# untitled.net
KiCad netlist of a schematic drawn in EAGLE
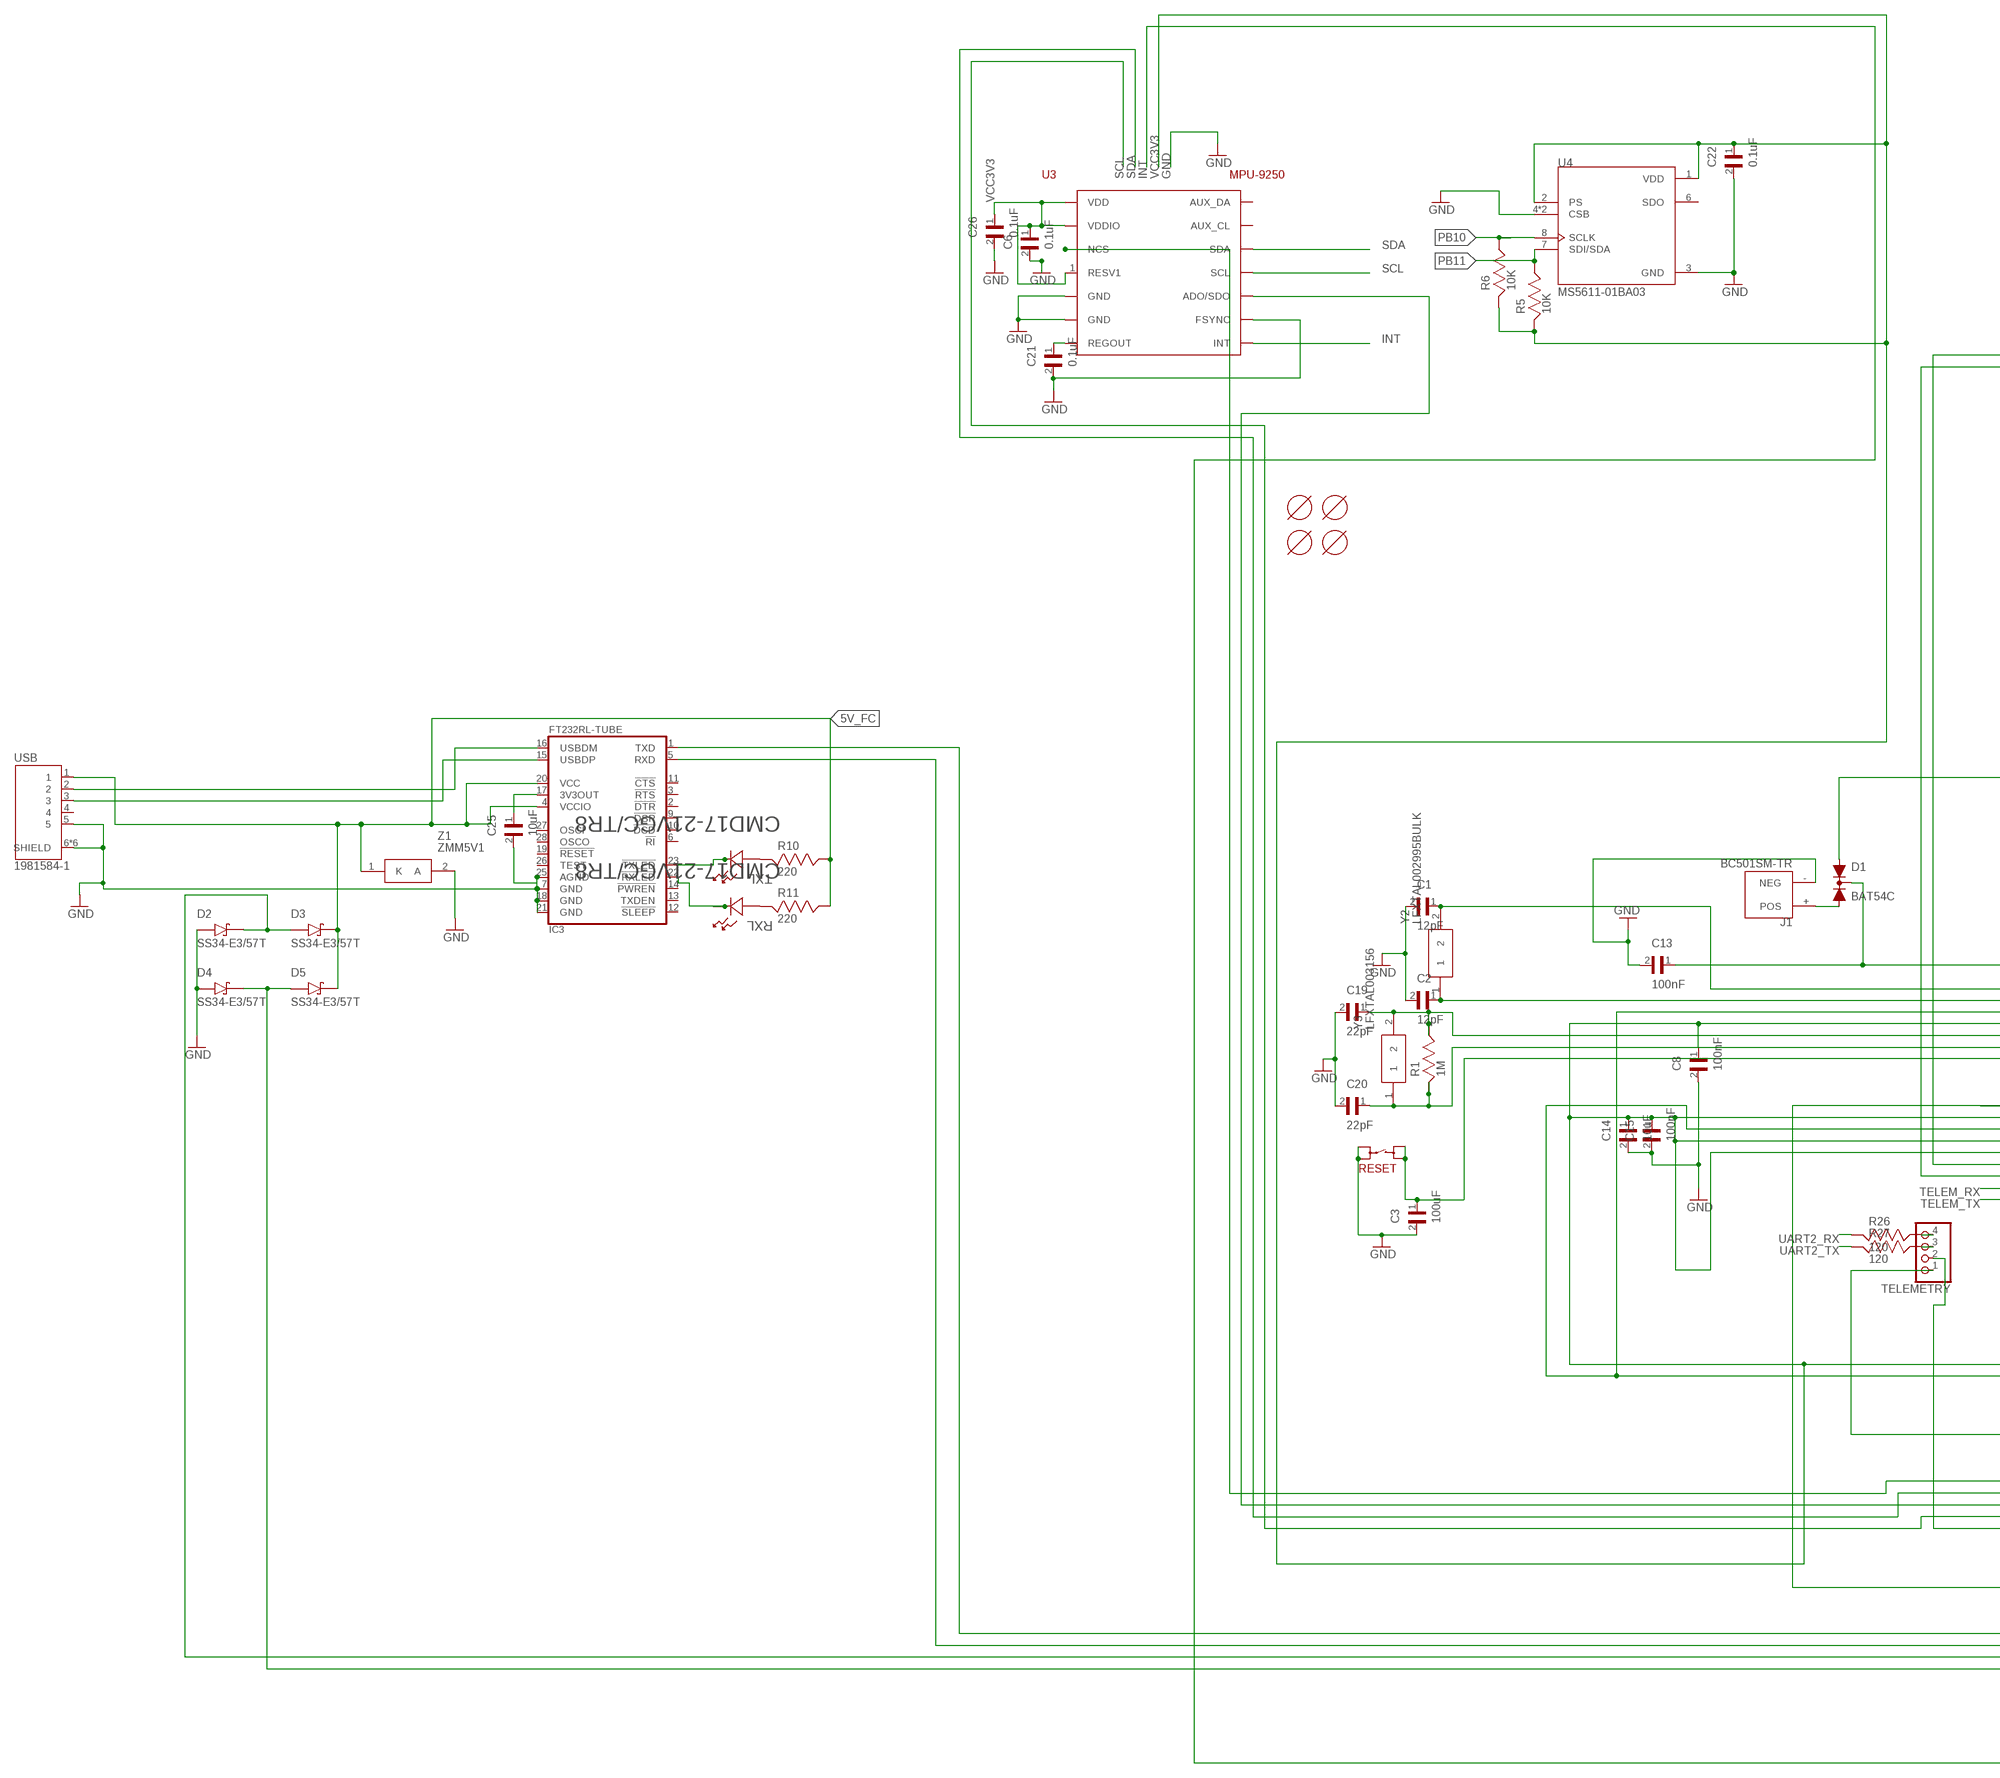
[diagram p0: schematic, sheet 1, part 1 of 2]
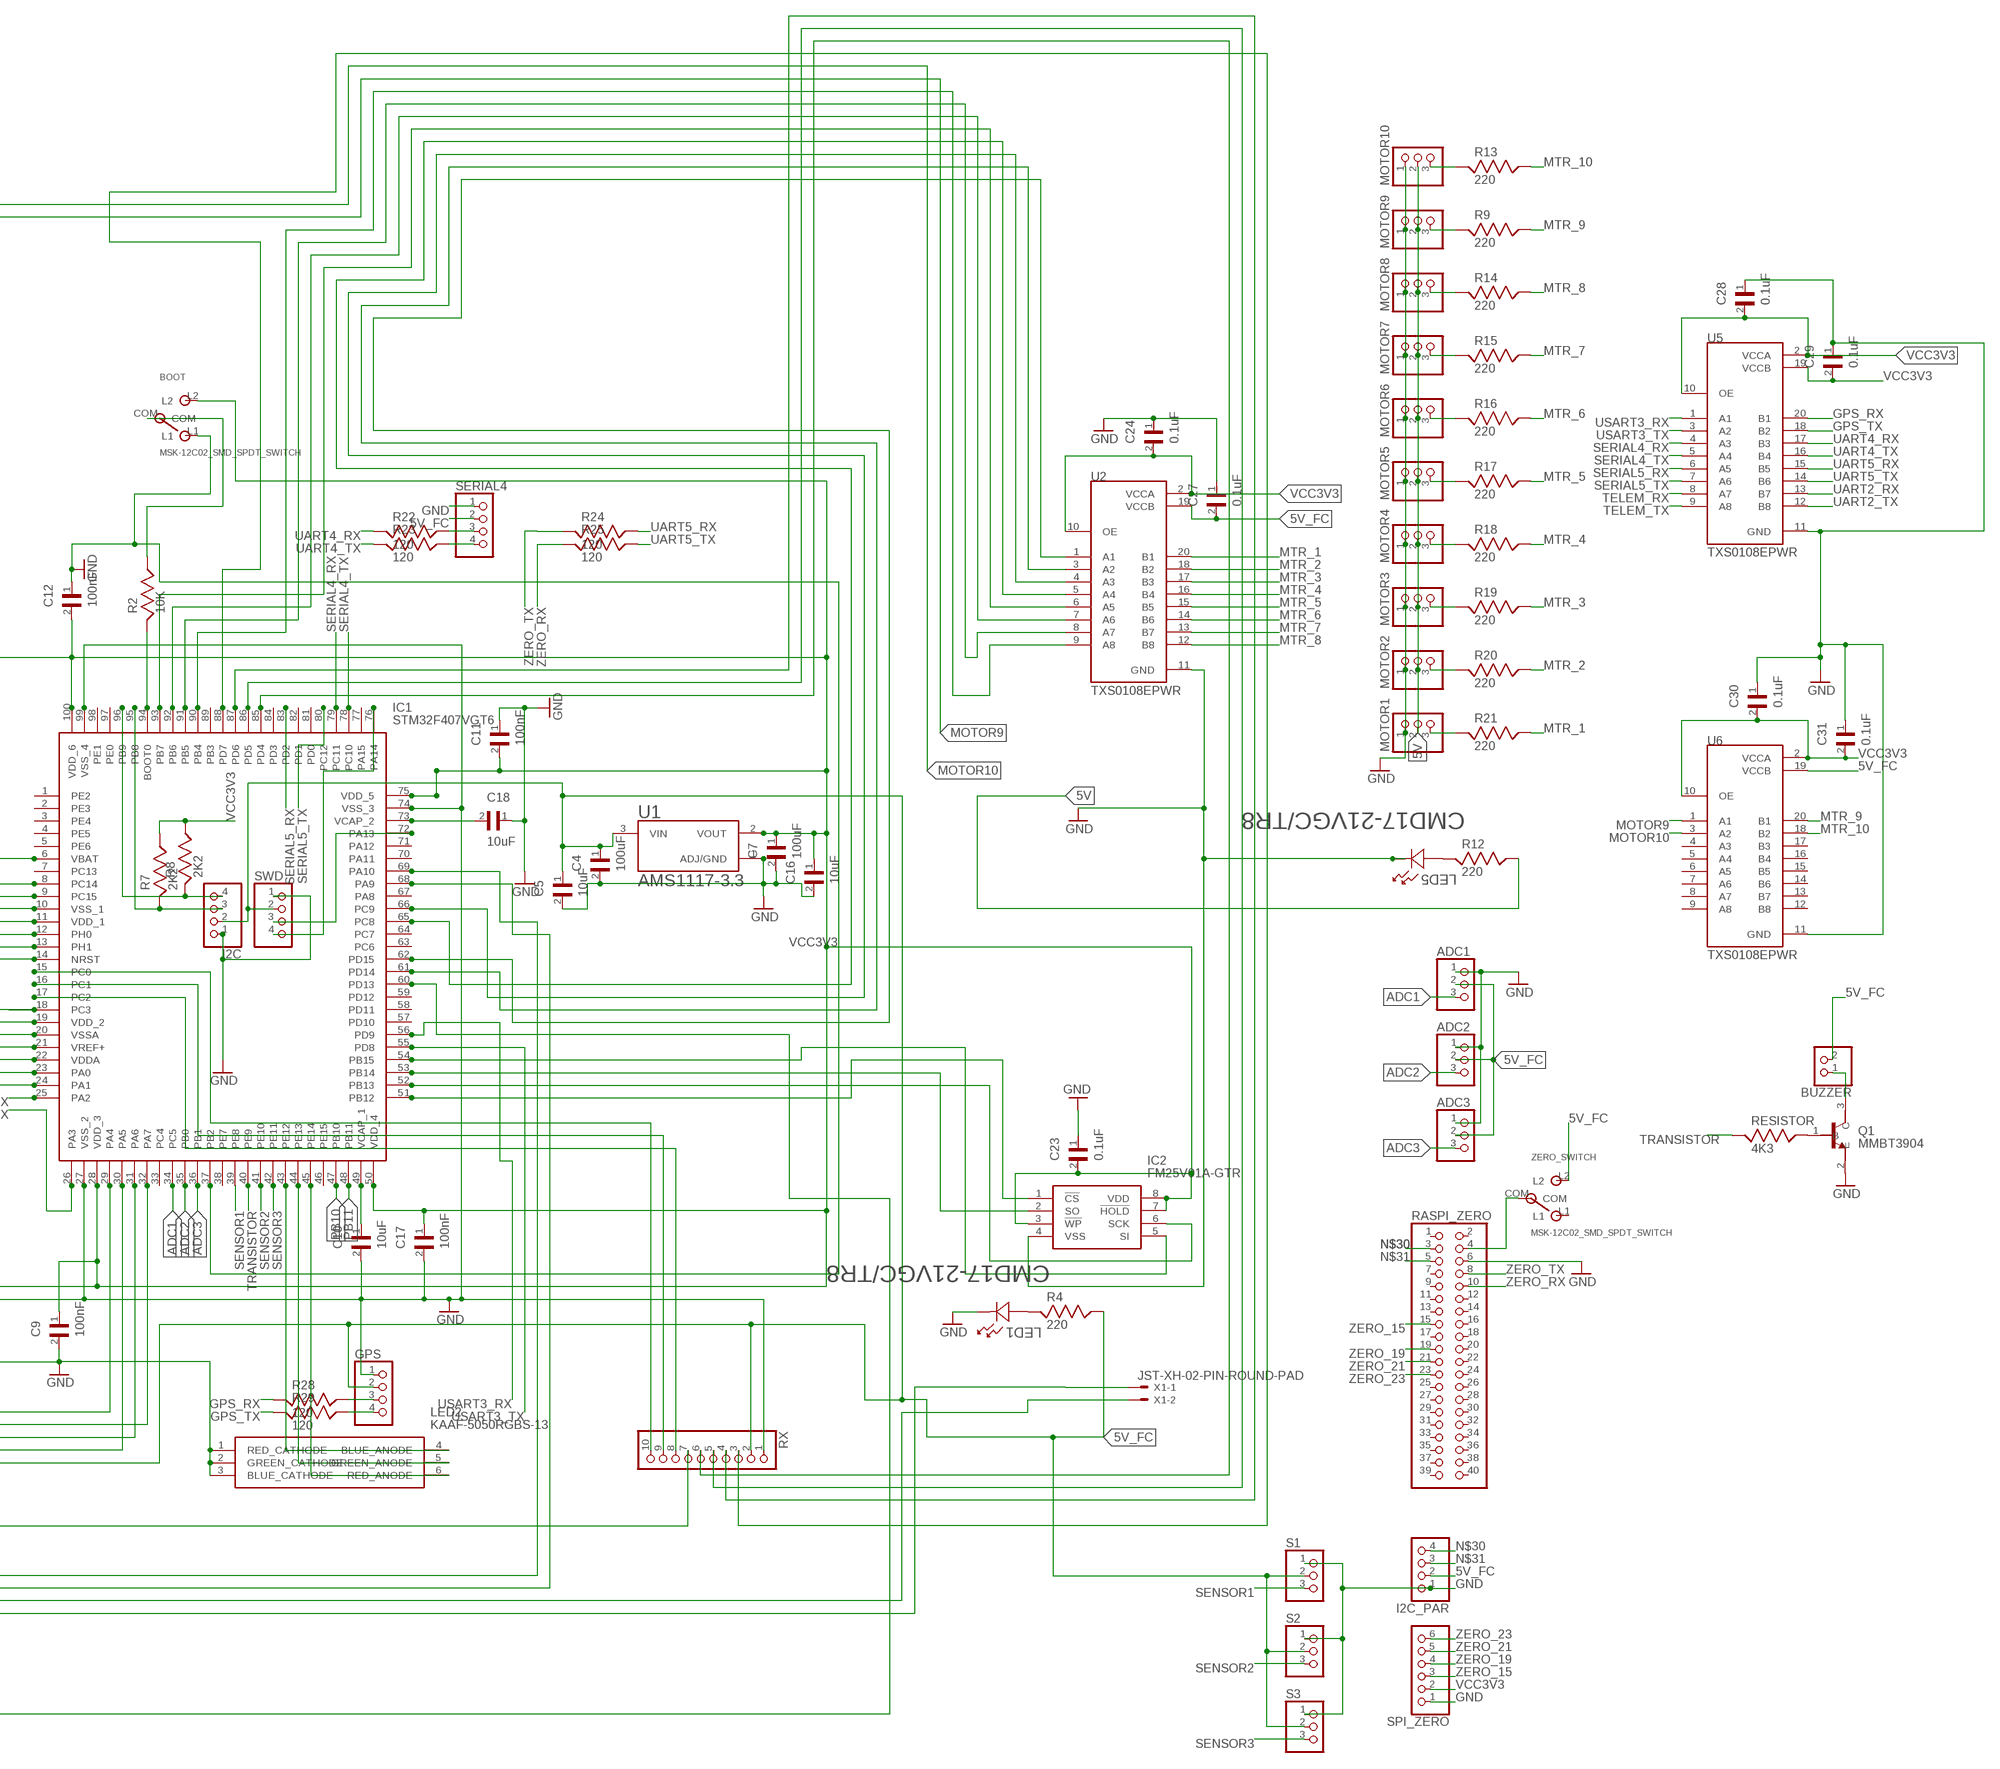
[diagram p1: schematic, sheet 1, part 2 of 2]

(export (version "E")
  (design (tool "Eeschema 10.0.6"))
  (components
    (comp (ref "ADC1")
      (value "PINHD-1X3")
      (footprint "eagle-import:1X03")
      (libsource (lib "eagle-import") (part "PINHD-1X3"))
    )
    (comp (ref "ADC2")
      (value "PINHD-1X3")
      (footprint "eagle-import:1X03")
      (libsource (lib "eagle-import") (part "PINHD-1X3"))
    )
    (comp (ref "ADC3")
      (value "PINHD-1X3")
      (footprint "eagle-import:1X03")
      (libsource (lib "eagle-import") (part "PINHD-1X3"))
    )
    (comp (ref "BOOT")
      (value "MSK-12C02_SMD_SPDT_SWITCH")
      (footprint "eagle-import:MSK-12C02")
      (libsource (lib "eagle-import") (part "MSK-12C02_SMD_SPDT_SWITCH"))
    )
    (comp (ref "BUZZER")
      (value "PINHD-1X2")
      (footprint "eagle-import:1X02")
      (libsource (lib "eagle-import") (part "PINHD-1X2"))
    )
    (comp (ref "C1")
      (value "12pF")
      (footprint "eagle-import:CAPC2012X94N")
      (fields (field (name "MF") "AVX") (field (name "MP") "08053C104KAT4A"))
      (libsource (lib "eagle-import") (part "08053C104KAT4A"))
    )
    (comp (ref "C2")
      (value "12pF")
      (footprint "eagle-import:CAPC2012X94N")
      (fields (field (name "MF") "AVX") (field (name "MP") "08053C104KAT4A"))
      (libsource (lib "eagle-import") (part "08053C104KAT4A"))
    )
    (comp (ref "C3")
      (value "100uF")
      (footprint "eagle-import:CAPC2012X94N")
      (fields (field (name "MF") "AVX") (field (name "MP") "08053C104KAT4A"))
      (libsource (lib "eagle-import") (part "08053C104KAT4A"))
    )
    (comp (ref "C4")
      (value "100uF")
      (footprint "eagle-import:CAPC2012X94N")
      (fields (field (name "MF") "AVX") (field (name "MP") "08053C104KAT4A"))
      (libsource (lib "eagle-import") (part "08053C104KAT4A"))
    )
    (comp (ref "C5")
      (value "10uF")
      (footprint "eagle-import:CAPC2012X94N")
      (fields (field (name "MF") "AVX") (field (name "MP") "08053C104KAT4A"))
      (libsource (lib "eagle-import") (part "08053C104KAT4A"))
    )
    (comp (ref "C6")
      (value "0.1uF")
      (footprint "eagle-import:CAPC2012X94N")
      (fields (field (name "MF") "AVX") (field (name "MP") "08053C104KAT4A"))
      (libsource (lib "eagle-import") (part "08053C104KAT4A"))
    )
    (comp (ref "C7")
      (value "100uF")
      (footprint "eagle-import:CAPC2012X94N")
      (fields (field (name "MF") "AVX") (field (name "MP") "08053C104KAT4A"))
      (libsource (lib "eagle-import") (part "08053C104KAT4A"))
    )
    (comp (ref "C8")
      (value "100nF")
      (footprint "eagle-import:CAPC2012X94N")
      (fields (field (name "MF") "AVX") (field (name "MP") "08053C104KAT4A"))
      (libsource (lib "eagle-import") (part "08053C104KAT4A"))
    )
    (comp (ref "C9")
      (value "100nF")
      (footprint "eagle-import:CAPC2012X94N")
      (fields (field (name "MF") "AVX") (field (name "MP") "08053C104KAT4A"))
      (libsource (lib "eagle-import") (part "08053C104KAT4A"))
    )
    (comp (ref "C10")
      (value "10uF")
      (footprint "eagle-import:CAPC2012X94N")
      (fields (field (name "MF") "AVX") (field (name "MP") "08053C104KAT4A"))
      (libsource (lib "eagle-import") (part "08053C104KAT4A"))
    )
    (comp (ref "C11")
      (value "100nF")
      (footprint "eagle-import:CAPC2012X94N")
      (fields (field (name "MF") "AVX") (field (name "MP") "08053C104KAT4A"))
      (libsource (lib "eagle-import") (part "08053C104KAT4A"))
    )
    (comp (ref "C12")
      (value "100nF")
      (footprint "eagle-import:CAPC2012X94N")
      (fields (field (name "MF") "AVX") (field (name "MP") "08053C104KAT4A"))
      (libsource (lib "eagle-import") (part "08053C104KAT4A"))
    )
    (comp (ref "C13")
      (value "100nF")
      (footprint "eagle-import:CAPC2012X94N")
      (fields (field (name "MF") "AVX") (field (name "MP") "08053C104KAT4A"))
      (libsource (lib "eagle-import") (part "08053C104KAT4A"))
    )
    (comp (ref "C14")
      (value "10uF")
      (footprint "eagle-import:CAPC2012X94N")
      (fields (field (name "MF") "AVX") (field (name "MP") "08053C104KAT4A"))
      (libsource (lib "eagle-import") (part "08053C104KAT4A"))
    )
    (comp (ref "C15")
      (value "100nF")
      (footprint "eagle-import:CAPC2012X94N")
      (fields (field (name "MF") "AVX") (field (name "MP") "08053C104KAT4A"))
      (libsource (lib "eagle-import") (part "08053C104KAT4A"))
    )
    (comp (ref "C16")
      (value "10uF")
      (footprint "eagle-import:CAPC2012X94N")
      (fields (field (name "MF") "AVX") (field (name "MP") "08053C104KAT4A"))
      (libsource (lib "eagle-import") (part "08053C104KAT4A"))
    )
    (comp (ref "C17")
      (value "100nF")
      (footprint "eagle-import:CAPC2012X94N")
      (fields (field (name "MF") "AVX") (field (name "MP") "08053C104KAT4A"))
      (libsource (lib "eagle-import") (part "08053C104KAT4A"))
    )
    (comp (ref "C18")
      (value "10uF")
      (footprint "eagle-import:CAPC2012X94N")
      (fields (field (name "MF") "AVX") (field (name "MP") "08053C104KAT4A"))
      (libsource (lib "eagle-import") (part "08053C104KAT4A"))
    )
    (comp (ref "C19")
      (value "22pF")
      (footprint "eagle-import:CAPC2012X94N")
      (fields (field (name "MF") "AVX") (field (name "MP") "08053C104KAT4A"))
      (libsource (lib "eagle-import") (part "08053C104KAT4A"))
    )
    (comp (ref "C20")
      (value "22pF")
      (footprint "eagle-import:CAPC2012X94N")
      (fields (field (name "MF") "AVX") (field (name "MP") "08053C104KAT4A"))
      (libsource (lib "eagle-import") (part "08053C104KAT4A"))
    )
    (comp (ref "C21")
      (value "0.1uF")
      (footprint "eagle-import:CAPC2012X94N")
      (fields (field (name "MF") "AVX") (field (name "MP") "08053C104KAT4A"))
      (libsource (lib "eagle-import") (part "08053C104KAT4A"))
    )
    (comp (ref "C22")
      (value "0.1uF")
      (footprint "eagle-import:CAPC2012X94N")
      (fields (field (name "MF") "AVX") (field (name "MP") "08053C104KAT4A"))
      (libsource (lib "eagle-import") (part "08053C104KAT4A"))
    )
    (comp (ref "C23")
      (value "0.1uF")
      (footprint "eagle-import:CAPC2012X94N")
      (fields (field (name "MF") "AVX") (field (name "MP") "08053C104KAT4A"))
      (libsource (lib "eagle-import") (part "08053C104KAT4A"))
    )
    (comp (ref "C24")
      (value "0.1uF")
      (footprint "eagle-import:CAPC2012X94N")
      (fields (field (name "MF") "AVX") (field (name "MP") "08053C104KAT4A"))
      (libsource (lib "eagle-import") (part "08053C104KAT4A"))
    )
    (comp (ref "C25")
      (value "10uF")
      (footprint "eagle-import:CAPC2012X94N")
      (fields (field (name "MF") "AVX") (field (name "MP") "08053C104KAT4A"))
      (libsource (lib "eagle-import") (part "08053C104KAT4A"))
    )
    (comp (ref "C26")
      (value "0.1uF")
      (footprint "eagle-import:CAPC2012X94N")
      (fields (field (name "MF") "AVX") (field (name "MP") "08053C104KAT4A"))
      (libsource (lib "eagle-import") (part "08053C104KAT4A"))
    )
    (comp (ref "C27")
      (value "0.1uF")
      (footprint "eagle-import:CAPC2012X94N")
      (fields (field (name "MF") "AVX") (field (name "MP") "08053C104KAT4A"))
      (libsource (lib "eagle-import") (part "08053C104KAT4A"))
    )
    (comp (ref "C28")
      (value "0.1uF")
      (footprint "eagle-import:CAPC2012X94N")
      (fields (field (name "MF") "AVX") (field (name "MP") "08053C104KAT4A"))
      (libsource (lib "eagle-import") (part "08053C104KAT4A"))
    )
    (comp (ref "C29")
      (value "0.1uF")
      (footprint "eagle-import:CAPC2012X94N")
      (fields (field (name "MF") "AVX") (field (name "MP") "08053C104KAT4A"))
      (libsource (lib "eagle-import") (part "08053C104KAT4A"))
    )
    (comp (ref "C30")
      (value "0.1uF")
      (footprint "eagle-import:CAPC2012X94N")
      (fields (field (name "MF") "AVX") (field (name "MP") "08053C104KAT4A"))
      (libsource (lib "eagle-import") (part "08053C104KAT4A"))
    )
    (comp (ref "C31")
      (value "0.1uF")
      (footprint "eagle-import:CAPC2012X94N")
      (fields (field (name "MF") "AVX") (field (name "MP") "08053C104KAT4A"))
      (libsource (lib "eagle-import") (part "08053C104KAT4A"))
    )
    (comp (ref "D1")
      (value "BAT54C")
      (footprint "eagle-import:SOT23-R")
      (fields (field (name "DIGI-KEY_PART_NUMBER") "BAT54CFSCT-ND") (field (name "MF") "ON Semiconductor"))
      (libsource (lib "eagle-import") (part "BAT54C"))
    )
    (comp (ref "D2")
      (value "SS34-E3/57T")
      (footprint "eagle-import:DIOM7959X262N")
      (fields (field (name "DIGI-KEY_PART_NUMBER") "SS34-E3/57TGICT-ND") (field (name "MF") "Vishay"))
      (libsource (lib "eagle-import") (part "SS34-E3/57T"))
    )
    (comp (ref "D3")
      (value "SS34-E3/57T")
      (footprint "eagle-import:DIOM7959X262N")
      (fields (field (name "DIGI-KEY_PART_NUMBER") "SS34-E3/57TGICT-ND") (field (name "MF") "Vishay"))
      (libsource (lib "eagle-import") (part "SS34-E3/57T"))
    )
    (comp (ref "D4")
      (value "SS34-E3/57T")
      (footprint "eagle-import:DIOM7959X262N")
      (fields (field (name "DIGI-KEY_PART_NUMBER") "SS34-E3/57TGICT-ND") (field (name "MF") "Vishay"))
      (libsource (lib "eagle-import") (part "SS34-E3/57T"))
    )
    (comp (ref "D5")
      (value "SS34-E3/57T")
      (footprint "eagle-import:DIOM7959X262N")
      (fields (field (name "DIGI-KEY_PART_NUMBER") "SS34-E3/57TGICT-ND") (field (name "MF") "Vishay"))
      (libsource (lib "eagle-import") (part "SS34-E3/57T"))
    )
    (comp (ref "GPS")
      (value "PINHD-1X4")
      (footprint "eagle-import:1X04")
      (libsource (lib "eagle-import") (part "PINHD-1X4"))
    )
    (comp (ref "I2C")
      (value "PINHD-1X4")
      (footprint "eagle-import:1X04")
      (libsource (lib "eagle-import") (part "PINHD-1X4"))
    )
    (comp (ref "I2C_PAR")
      (value "PINHD-1X4")
      (footprint "eagle-import:1X04")
      (libsource (lib "eagle-import") (part "PINHD-1X4"))
    )
    (comp (ref "IC1")
      (value "STM32F407VGT6")
      (footprint "eagle-import:QFP50P1600X1600X160-100N")
      (libsource (lib "eagle-import") (part "STM32F407VGT6"))
    )
    (comp (ref "IC2")
      (value "FM25V01A-GTR")
      (footprint "eagle-import:SOIC127P602X173-8N")
      (fields (field (name "MOUSER_PART_NUMBER") "727-FM25V01A-GTR"))
      (libsource (lib "eagle-import") (part "FM25V01A-GTR"))
    )
    (comp (ref "IC3")
      (value "FT232RL-TUBE")
      (footprint "eagle-import:SSOP28-LD")
      (fields (field (name "DIGI-KEY_PART_NUMBER") "768-1306-ND") (field (name "MF") "FTDI,"))
      (libsource (lib "eagle-import") (part "FT232RL-TUBE"))
    )
    (comp (ref "J1")
      (value "BC501SM-TR")
      (footprint "eagle-import:MPD_BC501SM-TR")
      (fields (field (name "MF") "MPD _Memory"))
      (libsource (lib "eagle-import") (part "BC501SM-TR"))
    )
    (comp (ref "LED1")
      (value "CMD17-21VGC/TR8")
      (footprint "eagle-import:LED_CMD17-21VGC_TR8")
      (fields (field (name "MF") "Visual"))
      (libsource (lib "eagle-import") (part "CMD17-21VGC/TR8"))
    )
    (comp (ref "LED2")
      (value "KAAF-5050RGBS-13")
      (footprint "eagle-import:KAAF-5050RGBS-13")
      (fields (field (name "RS_PART_NUMBER") "1654417"))
      (libsource (lib "eagle-import") (part "KAAF-5050RGBS-13"))
    )
    (comp (ref "LED5")
      (value "CMD17-21VGC/TR8")
      (footprint "eagle-import:LED_CMD17-21VGC_TR8")
      (fields (field (name "MF") "Visual"))
      (libsource (lib "eagle-import") (part "CMD17-21VGC/TR8"))
    )
    (comp (ref "M3_MOUNT1")
      (value "MOUNT-HOLE3.1MM")
      (footprint "eagle-import:MOUNT-HOLE3.1")
      (libsource (lib "eagle-import") (part "MOUNT-HOLE3.1MM"))
    )
    (comp (ref "M3_MOUNT1102")
      (value "MOUNT-HOLE3.1MM")
      (footprint "eagle-import:MOUNT-HOLE3.1")
      (libsource (lib "eagle-import") (part "MOUNT-HOLE3.1MM"))
    )
    (comp (ref "M3_MOUNT1103")
      (value "MOUNT-HOLE3.1MM")
      (footprint "eagle-import:MOUNT-HOLE3.1")
      (libsource (lib "eagle-import") (part "MOUNT-HOLE3.1MM"))
    )
    (comp (ref "M3_MOUNT1104")
      (value "MOUNT-HOLE3.1MM")
      (footprint "eagle-import:MOUNT-HOLE3.1")
      (libsource (lib "eagle-import") (part "MOUNT-HOLE3.1MM"))
    )
    (comp (ref "MOTOR1")
      (value "PINHD-1X3")
      (footprint "eagle-import:1X03")
      (libsource (lib "eagle-import") (part "PINHD-1X3"))
    )
    (comp (ref "MOTOR2")
      (value "PINHD-1X3")
      (footprint "eagle-import:1X03")
      (libsource (lib "eagle-import") (part "PINHD-1X3"))
    )
    (comp (ref "MOTOR3")
      (value "PINHD-1X3")
      (footprint "eagle-import:1X03")
      (libsource (lib "eagle-import") (part "PINHD-1X3"))
    )
    (comp (ref "MOTOR4")
      (value "PINHD-1X3")
      (footprint "eagle-import:1X03")
      (libsource (lib "eagle-import") (part "PINHD-1X3"))
    )
    (comp (ref "MOTOR5")
      (value "PINHD-1X3")
      (footprint "eagle-import:1X03")
      (libsource (lib "eagle-import") (part "PINHD-1X3"))
    )
    (comp (ref "MOTOR6")
      (value "PINHD-1X3")
      (footprint "eagle-import:1X03")
      (libsource (lib "eagle-import") (part "PINHD-1X3"))
    )
    (comp (ref "MOTOR7")
      (value "PINHD-1X3")
      (footprint "eagle-import:1X03")
      (libsource (lib "eagle-import") (part "PINHD-1X3"))
    )
    (comp (ref "MOTOR8")
      (value "PINHD-1X3")
      (footprint "eagle-import:1X03")
      (libsource (lib "eagle-import") (part "PINHD-1X3"))
    )
    (comp (ref "MOTOR9")
      (value "PINHD-1X3")
      (footprint "eagle-import:1X03")
      (libsource (lib "eagle-import") (part "PINHD-1X3"))
    )
    (comp (ref "MOTOR10")
      (value "PINHD-1X3")
      (footprint "eagle-import:1X03")
      (libsource (lib "eagle-import") (part "PINHD-1X3"))
    )
    (comp (ref "Q1")
      (value "MMBT3904")
      (footprint "eagle-import:SOT95P240X120-3N")
      (fields (field (name "MF") "STMicroelectronics"))
      (libsource (lib "eagle-import") (part "MMBT3904"))
    )
    (comp (ref "R1")
      (value "1M")
      (footprint "eagle-import:RESC2012X60")
      (fields (field (name "MF") "Yageo") (field (name "MP") "RC0805FR-078M2L"))
      (libsource (lib "eagle-import") (part "RC0805FR-078M2L"))
    )
    (comp (ref "R2")
      (value "10K")
      (footprint "eagle-import:RESC2012X60")
      (fields (field (name "MF") "Yageo") (field (name "MP") "RC0805FR-078M2L"))
      (libsource (lib "eagle-import") (part "RC0805FR-078M2L"))
    )
    (comp (ref "R4")
      (value "220")
      (footprint "eagle-import:RESC2012X60")
      (fields (field (name "MF") "Yageo") (field (name "MP") "RC0805FR-078M2L"))
      (libsource (lib "eagle-import") (part "RC0805FR-078M2L"))
    )
    (comp (ref "R5")
      (value "10K")
      (footprint "eagle-import:RESC2012X60")
      (fields (field (name "MF") "Yageo") (field (name "MP") "RC0805FR-078M2L"))
      (libsource (lib "eagle-import") (part "RC0805FR-078M2L"))
    )
    (comp (ref "R6")
      (value "10K")
      (footprint "eagle-import:RESC2012X60")
      (fields (field (name "MF") "Yageo") (field (name "MP") "RC0805FR-078M2L"))
      (libsource (lib "eagle-import") (part "RC0805FR-078M2L"))
    )
    (comp (ref "R7")
      (value "2K2")
      (footprint "eagle-import:RESC2012X60")
      (fields (field (name "MF") "Yageo") (field (name "MP") "RC0805FR-078M2L"))
      (libsource (lib "eagle-import") (part "RC0805FR-078M2L"))
    )
    (comp (ref "R8")
      (value "2K2")
      (footprint "eagle-import:RESC2012X60")
      (fields (field (name "MF") "Yageo") (field (name "MP") "RC0805FR-078M2L"))
      (libsource (lib "eagle-import") (part "RC0805FR-078M2L"))
    )
    (comp (ref "R9")
      (value "220")
      (footprint "eagle-import:RESC2012X60")
      (fields (field (name "MF") "Yageo") (field (name "MP") "RC0805FR-078M2L"))
      (libsource (lib "eagle-import") (part "RC0805FR-078M2L"))
    )
    (comp (ref "R10")
      (value "220")
      (footprint "eagle-import:RESC2012X60")
      (fields (field (name "MF") "Yageo") (field (name "MP") "RC0805FR-078M2L"))
      (libsource (lib "eagle-import") (part "RC0805FR-078M2L"))
    )
    (comp (ref "R11")
      (value "220")
      (footprint "eagle-import:RESC2012X60")
      (fields (field (name "MF") "Yageo") (field (name "MP") "RC0805FR-078M2L"))
      (libsource (lib "eagle-import") (part "RC0805FR-078M2L"))
    )
    (comp (ref "R12")
      (value "220")
      (footprint "eagle-import:RESC2012X60")
      (fields (field (name "MF") "Yageo") (field (name "MP") "RC0805FR-078M2L"))
      (libsource (lib "eagle-import") (part "RC0805FR-078M2L"))
    )
    (comp (ref "R13")
      (value "220")
      (footprint "eagle-import:RESC2012X60")
      (fields (field (name "MF") "Yageo") (field (name "MP") "RC0805FR-078M2L"))
      (libsource (lib "eagle-import") (part "RC0805FR-078M2L"))
    )
    (comp (ref "R14")
      (value "220")
      (footprint "eagle-import:RESC2012X60")
      (fields (field (name "MF") "Yageo") (field (name "MP") "RC0805FR-078M2L"))
      (libsource (lib "eagle-import") (part "RC0805FR-078M2L"))
    )
    (comp (ref "R15")
      (value "220")
      (footprint "eagle-import:RESC2012X60")
      (fields (field (name "MF") "Yageo") (field (name "MP") "RC0805FR-078M2L"))
      (libsource (lib "eagle-import") (part "RC0805FR-078M2L"))
    )
    (comp (ref "R16")
      (value "220")
      (footprint "eagle-import:RESC2012X60")
      (fields (field (name "MF") "Yageo") (field (name "MP") "RC0805FR-078M2L"))
      (libsource (lib "eagle-import") (part "RC0805FR-078M2L"))
    )
    (comp (ref "R17")
      (value "220")
      (footprint "eagle-import:RESC2012X60")
      (fields (field (name "MF") "Yageo") (field (name "MP") "RC0805FR-078M2L"))
      (libsource (lib "eagle-import") (part "RC0805FR-078M2L"))
    )
    (comp (ref "R18")
      (value "220")
      (footprint "eagle-import:RESC2012X60")
      (fields (field (name "MF") "Yageo") (field (name "MP") "RC0805FR-078M2L"))
      (libsource (lib "eagle-import") (part "RC0805FR-078M2L"))
    )
    (comp (ref "R19")
      (value "220")
      (footprint "eagle-import:RESC2012X60")
      (fields (field (name "MF") "Yageo") (field (name "MP") "RC0805FR-078M2L"))
      (libsource (lib "eagle-import") (part "RC0805FR-078M2L"))
    )
    (comp (ref "R20")
      (value "220")
      (footprint "eagle-import:RESC2012X60")
      (fields (field (name "MF") "Yageo") (field (name "MP") "RC0805FR-078M2L"))
      (libsource (lib "eagle-import") (part "RC0805FR-078M2L"))
    )
    (comp (ref "R21")
      (value "220")
      (footprint "eagle-import:RESC2012X60")
      (fields (field (name "MF") "Yageo") (field (name "MP") "RC0805FR-078M2L"))
      (libsource (lib "eagle-import") (part "RC0805FR-078M2L"))
    )
    (comp (ref "R22")
      (value "120")
      (footprint "eagle-import:RESC2012X60")
      (fields (field (name "MF") "Yageo") (field (name "MP") "RC0805FR-078M2L"))
      (libsource (lib "eagle-import") (part "RC0805FR-078M2L"))
    )
    (comp (ref "R23")
      (value "120")
      (footprint "eagle-import:RESC2012X60")
      (fields (field (name "MF") "Yageo") (field (name "MP") "RC0805FR-078M2L"))
      (libsource (lib "eagle-import") (part "RC0805FR-078M2L"))
    )
    (comp (ref "R24")
      (value "120")
      (footprint "eagle-import:RESC2012X60")
      (fields (field (name "MF") "Yageo") (field (name "MP") "RC0805FR-078M2L"))
      (libsource (lib "eagle-import") (part "RC0805FR-078M2L"))
    )
    (comp (ref "R25")
      (value "120")
      (footprint "eagle-import:RESC2012X60")
      (fields (field (name "MF") "Yageo") (field (name "MP") "RC0805FR-078M2L"))
      (libsource (lib "eagle-import") (part "RC0805FR-078M2L"))
    )
    (comp (ref "R26")
      (value "120")
      (footprint "eagle-import:RESC2012X60")
      (fields (field (name "MF") "Yageo") (field (name "MP") "RC0805FR-078M2L"))
      (libsource (lib "eagle-import") (part "RC0805FR-078M2L"))
    )
    (comp (ref "R27")
      (value "120")
      (footprint "eagle-import:RESC2012X60")
      (fields (field (name "MF") "Yageo") (field (name "MP") "RC0805FR-078M2L"))
      (libsource (lib "eagle-import") (part "RC0805FR-078M2L"))
    )
    (comp (ref "R28")
      (value "120")
      (footprint "eagle-import:RESC2012X60")
      (fields (field (name "MF") "Yageo") (field (name "MP") "RC0805FR-078M2L"))
      (libsource (lib "eagle-import") (part "RC0805FR-078M2L"))
    )
    (comp (ref "R29")
      (value "120")
      (footprint "eagle-import:RESC2012X60")
      (fields (field (name "MF") "Yageo") (field (name "MP") "RC0805FR-078M2L"))
      (libsource (lib "eagle-import") (part "RC0805FR-078M2L"))
    )
    (comp (ref "RASPI_ZERO")
      (value "PINHD-2X20")
      (footprint "eagle-import:2X20")
      (libsource (lib "eagle-import") (part "PINHD-2X20"))
    )
    (comp (ref "RESET")
      (value "SKRPABE010")
      (footprint "eagle-import:SKRPABE010")
      (fields (field (name "MF") "ALPS"))
      (libsource (lib "eagle-import") (part "SKRPABE010"))
    )
    (comp (ref "RESISTOR")
      (value "4K3")
      (footprint "eagle-import:RESC2012X60")
      (fields (field (name "MF") "Yageo") (field (name "MP") "RC0805FR-078M2L"))
      (libsource (lib "eagle-import") (part "RC0805FR-078M2L"))
    )
    (comp (ref "RX")
      (value "PINHD-1X10")
      (footprint "eagle-import:1X10")
      (libsource (lib "eagle-import") (part "PINHD-1X10"))
    )
    (comp (ref "RXL")
      (value "CMD17-21VGC/TR8")
      (footprint "eagle-import:LED_CMD17-21VGC_TR8")
      (fields (field (name "MF") "Visual"))
      (libsource (lib "eagle-import") (part "CMD17-21VGC/TR8"))
    )
    (comp (ref "S1")
      (value "PINHD-1X3")
      (footprint "eagle-import:1X03")
      (libsource (lib "eagle-import") (part "PINHD-1X3"))
    )
    (comp (ref "S2")
      (value "PINHD-1X3")
      (footprint "eagle-import:1X03")
      (libsource (lib "eagle-import") (part "PINHD-1X3"))
    )
    (comp (ref "S3")
      (value "PINHD-1X3")
      (footprint "eagle-import:1X03")
      (libsource (lib "eagle-import") (part "PINHD-1X3"))
    )
    (comp (ref "SERIAL4")
      (value "PINHD-1X4")
      (footprint "eagle-import:1X04")
      (libsource (lib "eagle-import") (part "PINHD-1X4"))
    )
    (comp (ref "SPI_ZERO")
      (value "PINHD-1X6")
      (footprint "eagle-import:1X06")
      (libsource (lib "eagle-import") (part "PINHD-1X6"))
    )
    (comp (ref "SWD")
      (value "PINHD-1X4")
      (footprint "eagle-import:1X04")
      (libsource (lib "eagle-import") (part "PINHD-1X4"))
    )
    (comp (ref "TELEMETRY")
      (value "PINHD-1X4")
      (footprint "eagle-import:1X04")
      (libsource (lib "eagle-import") (part "PINHD-1X4"))
    )
    (comp (ref "TXL")
      (value "CMD17-21VGC/TR8")
      (footprint "eagle-import:LED_CMD17-21VGC_TR8")
      (fields (field (name "MF") "Visual"))
      (libsource (lib "eagle-import") (part "CMD17-21VGC/TR8"))
    )
    (comp (ref "U1")
      (value "AMS1117-3.3")
      (footprint "eagle-import:SOT229P700X180-4N")
      (fields (field (name "MF") "Advanced Monolithic Systems"))
      (libsource (lib "eagle-import") (part "AMS1117-3.3"))
    )
    (comp (ref "U2")
      (value "TXS0108EPWR")
      (footprint "eagle-import:SOP65P640X120-20N")
      (fields (field (name "MF") "Texas Instruments"))
      (libsource (lib "eagle-import") (part "TXS0108EPWR"))
    )
    (comp (ref "U3")
      (value "MPU-9250")
      (footprint "eagle-import:MPU-9250")
      (libsource (lib "eagle-import") (part "MPU-9250"))
    )
    (comp (ref "U4")
      (value "MS5611-01BA03")
      (footprint "eagle-import:SON125P500X300X100-8N")
      (fields (field (name "MF") "TE Connectivity"))
      (libsource (lib "eagle-import") (part "MS5611-01BA03"))
    )
    (comp (ref "U5")
      (value "TXS0108EPWR")
      (footprint "eagle-import:SOP65P640X120-20N")
      (fields (field (name "MF") "Texas Instruments"))
      (libsource (lib "eagle-import") (part "TXS0108EPWR"))
    )
    (comp (ref "U6")
      (value "TXS0108EPWR")
      (footprint "eagle-import:SOP65P640X120-20N")
      (fields (field (name "MF") "Texas Instruments"))
      (libsource (lib "eagle-import") (part "TXS0108EPWR"))
    )
    (comp (ref "USB")
      (value "1981584-1")
      (footprint "eagle-import:TE_1981584-1")
      (fields (field (name "MF") "TE Connectivity"))
      (libsource (lib "eagle-import") (part "1981584-1"))
    )
    (comp (ref "X1")
      (value "JST-XH-02-PIN-ROUND-PAD")
      (footprint "eagle-import:JST-XH-02-PACKAGE-ROUND-PAD")
      (libsource (lib "eagle-import") (part "JST-XH-02-PIN-ROUND-PAD"))
    )
    (comp (ref "Y2")
      (value "LFXTAL002995BULK")
      (footprint "eagle-import:LFXTAL002995BULK")
      (fields
        (field (name "MANUFACTURER_PART_NUMBER") "LFXTAL002995Bulk")
        (field (name "MOUSER_PART_NUMBER") "449-LFXTAL002995BULK")
      )
      (libsource (lib "eagle-import") (part "LFXTAL002995BULK"))
    )
    (comp (ref "Y3")
      (value "LFXTAL003156")
      (footprint "eagle-import:IQD-HC-49-4H")
      (fields (field (name "RS_PART_NUMBER") "1533666"))
      (libsource (lib "eagle-import") (part "LFXTAL003156"))
    )
    (comp (ref "Z1")
      (value "ZMM5V1")
      (footprint "eagle-import:ZMM5V1")
      (libsource (lib "eagle-import") (part "ZMM5V1"))
    )
    (comp (ref "ZERO_SWITCH")
      (value "MSK-12C02_SMD_SPDT_SWITCH")
      (footprint "eagle-import:MSK-12C02")
      (libsource (lib "eagle-import") (part "MSK-12C02_SMD_SPDT_SWITCH"))
    )
  )
  (nets
    (net (code "1") (name "/GPS_RX") (class "Default")
      (node (ref "R28") (pin "1") (pinfunction "1_1") (pintype "passive"))
      (node (ref "U5") (pin "20") (pinfunction "B1_20") (pintype "bidirectional"))
    )
    (net (code "2") (name "/GPS_TX") (class "Default")
      (node (ref "R29") (pin "1") (pinfunction "1_1") (pintype "passive"))
      (node (ref "U5") (pin "18") (pinfunction "B2_18") (pintype "bidirectional"))
    )
    (net (code "3") (name "/INT") (class "Default")
      (node (ref "IC1") (pin "60") (pinfunction "PD13_60") (pintype "bidirectional"))
      (node (ref "U3") (pin "12") (pinfunction "INT_12") (pintype "bidirectional"))
    )
    (net (code "4") (name "/MTR_1") (class "Default")
      (node (ref "R21") (pin "2") (pinfunction "2_2") (pintype "passive"))
      (node (ref "U2") (pin "20") (pinfunction "B1_20") (pintype "bidirectional"))
    )
    (net (code "5") (name "/MTR_2") (class "Default")
      (node (ref "R20") (pin "2") (pinfunction "2_2") (pintype "passive"))
      (node (ref "U2") (pin "18") (pinfunction "B2_18") (pintype "bidirectional"))
    )
    (net (code "6") (name "/MTR_3") (class "Default")
      (node (ref "R19") (pin "2") (pinfunction "2_2") (pintype "passive"))
      (node (ref "U2") (pin "17") (pinfunction "B3_17") (pintype "bidirectional"))
    )
    (net (code "7") (name "/MTR_4") (class "Default")
      (node (ref "R18") (pin "2") (pinfunction "2_2") (pintype "passive"))
      (node (ref "U2") (pin "16") (pinfunction "B4_16") (pintype "bidirectional"))
    )
    (net (code "8") (name "/MTR_5") (class "Default")
      (node (ref "R17") (pin "2") (pinfunction "2_2") (pintype "passive"))
      (node (ref "U2") (pin "15") (pinfunction "B5_15") (pintype "bidirectional"))
    )
    (net (code "9") (name "/MTR_6") (class "Default")
      (node (ref "R16") (pin "2") (pinfunction "2_2") (pintype "passive"))
      (node (ref "U2") (pin "14") (pinfunction "B6_14") (pintype "bidirectional"))
    )
    (net (code "10") (name "/MTR_7") (class "Default")
      (node (ref "R15") (pin "2") (pinfunction "2_2") (pintype "passive"))
      (node (ref "U2") (pin "13") (pinfunction "B7_13") (pintype "bidirectional"))
    )
    (net (code "11") (name "/MTR_8") (class "Default")
      (node (ref "R14") (pin "2") (pinfunction "2_2") (pintype "passive"))
      (node (ref "U2") (pin "12") (pinfunction "B8_12") (pintype "bidirectional"))
    )
    (net (code "12") (name "/MTR_9") (class "Default")
      (node (ref "R9") (pin "2") (pinfunction "2_2") (pintype "passive"))
      (node (ref "U6") (pin "20") (pinfunction "B1_20") (pintype "bidirectional"))
    )
    (net (code "13") (name "/MTR_10") (class "Default")
      (node (ref "R13") (pin "2") (pinfunction "2_2") (pintype "passive"))
      (node (ref "U6") (pin "18") (pinfunction "B2_18") (pintype "bidirectional"))
    )
    (net (code "14") (name "/N$30") (class "Default")
      (node (ref "I2C") (pin "4") (pinfunction "4_4") (pintype "passive"))
      (node (ref "I2C_PAR") (pin "4") (pinfunction "4_4") (pintype "passive"))
      (node (ref "IC1") (pin "96") (pinfunction "PB9_96") (pintype "bidirectional"))
      (node (ref "R8") (pin "1") (pinfunction "1_1") (pintype "passive"))
      (node (ref "RASPI_ZERO") (pin "3") (pinfunction "3_3") (pintype "passive"))
    )
    (net (code "15") (name "/N$31") (class "Default")
      (node (ref "I2C") (pin "3") (pinfunction "3_3") (pintype "passive"))
      (node (ref "I2C_PAR") (pin "3") (pinfunction "3_3") (pintype "passive"))
      (node (ref "IC1") (pin "95") (pinfunction "PB8_95") (pintype "bidirectional"))
      (node (ref "R7") (pin "1") (pinfunction "1_1") (pintype "passive"))
      (node (ref "RASPI_ZERO") (pin "5") (pinfunction "5_5") (pintype "passive"))
    )
    (net (code "16") (name "/SCL") (class "Default")
      (node (ref "IC1") (pin "30") (pinfunction "PA5_30") (pintype "bidirectional"))
      (node (ref "U3") (pin "23") (pinfunction "SCL_23") (pintype "bidirectional"))
    )
    (net (code "17") (name "/SDA") (class "Default")
      (node (ref "IC1") (pin "32") (pinfunction "PA7_32") (pintype "bidirectional"))
      (node (ref "U3") (pin "24") (pinfunction "SDA_24") (pintype "bidirectional"))
    )
    (net (code "18") (name "/SENSOR1") (class "Default")
      (node (ref "IC1") (pin "39") (pinfunction "PE8_39") (pintype "bidirectional"))
      (node (ref "S1") (pin "3") (pinfunction "3_3") (pintype "passive"))
    )
    (net (code "19") (name "/SENSOR2") (class "Default")
      (node (ref "IC1") (pin "41") (pinfunction "PE10_41") (pintype "bidirectional"))
      (node (ref "S2") (pin "3") (pinfunction "3_3") (pintype "passive"))
    )
    (net (code "20") (name "/SENSOR3") (class "Default")
      (node (ref "IC1") (pin "42") (pinfunction "PE11_42") (pintype "bidirectional"))
      (node (ref "S3") (pin "3") (pinfunction "3_3") (pintype "passive"))
    )
    (net (code "21") (name "/SERIAL4_RX") (class "Default")
      (node (ref "IC1") (pin "79") (pinfunction "PC11_79") (pintype "bidirectional"))
      (node (ref "U5") (pin "4") (pinfunction "A3_4") (pintype "bidirectional"))
    )
    (net (code "22") (name "/SERIAL4_TX") (class "Default")
      (node (ref "IC1") (pin "78") (pinfunction "PC10_78") (pintype "bidirectional"))
      (node (ref "U5") (pin "5") (pinfunction "A4_5") (pintype "bidirectional"))
    )
    (net (code "23") (name "/SERIAL5_RX") (class "Default")
      (node (ref "IC1") (pin "83") (pinfunction "PD2_83") (pintype "bidirectional"))
      (node (ref "U5") (pin "6") (pinfunction "A5_6") (pintype "bidirectional"))
    )
    (net (code "24") (name "/SERIAL5_TX") (class "Default")
      (node (ref "IC1") (pin "80") (pinfunction "PC12_80") (pintype "bidirectional"))
      (node (ref "U5") (pin "7") (pinfunction "A6_7") (pintype "bidirectional"))
    )
    (net (code "25") (name "/TELEM_RX") (class "Default")
      (node (ref "IC1") (pin "25") (pinfunction "PA2_25") (pintype "bidirectional"))
      (node (ref "U5") (pin "8") (pinfunction "A7_8") (pintype "bidirectional"))
    )
    (net (code "26") (name "/TELEM_TX") (class "Default")
      (node (ref "IC1") (pin "26") (pinfunction "PA3_26") (pintype "bidirectional"))
      (node (ref "U5") (pin "9") (pinfunction "A8_9") (pintype "bidirectional"))
    )
    (net (code "27") (name "/TRANSISTOR") (class "Default")
      (node (ref "IC1") (pin "40") (pinfunction "PE9_40") (pintype "bidirectional"))
      (node (ref "RESISTOR") (pin "1") (pinfunction "1_1") (pintype "passive"))
    )
    (net (code "28") (name "/UART2_RX") (class "Default")
      (node (ref "R26") (pin "1") (pinfunction "1_1") (pintype "passive"))
      (node (ref "U5") (pin "13") (pinfunction "B7_13") (pintype "bidirectional"))
    )
    (net (code "29") (name "/UART2_TX") (class "Default")
      (node (ref "R27") (pin "1") (pinfunction "1_1") (pintype "passive"))
      (node (ref "U5") (pin "12") (pinfunction "B8_12") (pintype "bidirectional"))
    )
    (net (code "30") (name "/UART4_RX") (class "Default")
      (node (ref "R22") (pin "1") (pinfunction "1_1") (pintype "passive"))
      (node (ref "U5") (pin "17") (pinfunction "B3_17") (pintype "bidirectional"))
    )
    (net (code "31") (name "/UART4_TX") (class "Default")
      (node (ref "R23") (pin "1") (pinfunction "1_1") (pintype "passive"))
      (node (ref "U5") (pin "16") (pinfunction "B4_16") (pintype "bidirectional"))
    )
    (net (code "32") (name "/UART5_RX") (class "Default")
      (node (ref "R24") (pin "2") (pinfunction "2_2") (pintype "passive"))
      (node (ref "U5") (pin "15") (pinfunction "B5_15") (pintype "bidirectional"))
    )
    (net (code "33") (name "/UART5_TX") (class "Default")
      (node (ref "R25") (pin "2") (pinfunction "2_2") (pintype "passive"))
      (node (ref "U5") (pin "14") (pinfunction "B6_14") (pintype "bidirectional"))
    )
    (net (code "34") (name "/USART3_RX") (class "Default")
      (node (ref "IC1") (pin "56") (pinfunction "PD9_56") (pintype "bidirectional"))
      (node (ref "U5") (pin "1") (pinfunction "A1_1") (pintype "bidirectional"))
    )
    (net (code "35") (name "/USART3_TX") (class "Default")
      (node (ref "IC1") (pin "55") (pinfunction "PD8_55") (pintype "bidirectional"))
      (node (ref "U5") (pin "3") (pinfunction "A2_3") (pintype "bidirectional"))
    )
    (net (code "36") (name "/ZERO_15") (class "Default")
      (node (ref "RASPI_ZERO") (pin "15") (pinfunction "15_15") (pintype "passive"))
      (node (ref "SPI_ZERO") (pin "3") (pinfunction "3_3") (pintype "passive"))
    )
    (net (code "37") (name "/ZERO_19") (class "Default")
      (node (ref "RASPI_ZERO") (pin "19") (pinfunction "19_19") (pintype "passive"))
      (node (ref "SPI_ZERO") (pin "4") (pinfunction "4_4") (pintype "passive"))
    )
    (net (code "38") (name "/ZERO_21") (class "Default")
      (node (ref "RASPI_ZERO") (pin "21") (pinfunction "21_21") (pintype "passive"))
      (node (ref "SPI_ZERO") (pin "5") (pinfunction "5_5") (pintype "passive"))
    )
    (net (code "39") (name "/ZERO_23") (class "Default")
      (node (ref "RASPI_ZERO") (pin "23") (pinfunction "23_23") (pintype "passive"))
      (node (ref "SPI_ZERO") (pin "6") (pinfunction "6_6") (pintype "passive"))
    )
    (net (code "40") (name "/ZERO_RX") (class "Default")
      (node (ref "R25") (pin "1") (pinfunction "1_1") (pintype "passive"))
      (node (ref "RASPI_ZERO") (pin "10") (pinfunction "10_10") (pintype "passive"))
    )
    (net (code "41") (name "/ZERO_TX") (class "Default")
      (node (ref "R24") (pin "1") (pinfunction "1_1") (pintype "passive"))
      (node (ref "RASPI_ZERO") (pin "8") (pinfunction "8_8") (pintype "passive"))
    )
    (net (code "42") (name "5V") (class "Default")
      (node (ref "MOTOR1") (pin "2") (pinfunction "2_2") (pintype "passive"))
      (node (ref "MOTOR10") (pin "2") (pinfunction "2_2") (pintype "passive"))
      (node (ref "MOTOR2") (pin "2") (pinfunction "2_2") (pintype "passive"))
      (node (ref "MOTOR3") (pin "2") (pinfunction "2_2") (pintype "passive"))
      (node (ref "MOTOR4") (pin "2") (pinfunction "2_2") (pintype "passive"))
      (node (ref "MOTOR5") (pin "2") (pinfunction "2_2") (pintype "passive"))
      (node (ref "MOTOR6") (pin "2") (pinfunction "2_2") (pintype "passive"))
      (node (ref "MOTOR7") (pin "2") (pinfunction "2_2") (pintype "passive"))
      (node (ref "MOTOR8") (pin "2") (pinfunction "2_2") (pintype "passive"))
      (node (ref "MOTOR9") (pin "2") (pinfunction "2_2") (pintype "passive"))
      (node (ref "R12") (pin "2") (pinfunction "2_2") (pintype "passive"))
    )
    (net (code "43") (name "5V_FC") (class "Default")
      (node (ref "ADC1") (pin "2") (pinfunction "2_2") (pintype "passive"))
      (node (ref "ADC2") (pin "2") (pinfunction "2_2") (pintype "passive"))
      (node (ref "ADC3") (pin "2") (pinfunction "2_2") (pintype "passive"))
      (node (ref "BUZZER") (pin "2") (pinfunction "2_2") (pintype "passive"))
      (node (ref "C27") (pin "2") (pinfunction "2_2") (pintype "passive"))
      (node (ref "C4") (pin "1") (pinfunction "1_1") (pintype "passive"))
      (node (ref "C5") (pin "1") (pinfunction "1_1") (pintype "passive"))
      (node (ref "D3") (pin "C") (pinfunction "C_C") (pintype "passive"))
      (node (ref "D5") (pin "C") (pinfunction "C_C") (pintype "passive"))
      (node (ref "GPS") (pin "2") (pinfunction "2_2") (pintype "passive"))
      (node (ref "I2C") (pin "2") (pinfunction "2_2") (pintype "passive"))
      (node (ref "I2C_PAR") (pin "2") (pinfunction "2_2") (pintype "passive"))
      (node (ref "IC3") (pin "20") (pinfunction "VCC_20") (pintype "power_in"))
      (node (ref "IC3") (pin "4") (pinfunction "VCCIO_4") (pintype "power_in"))
      (node (ref "R10") (pin "2") (pinfunction "2_2") (pintype "passive"))
      (node (ref "R11") (pin "2") (pinfunction "2_2") (pintype "passive"))
      (node (ref "R4") (pin "2") (pinfunction "2_2") (pintype "passive"))
      (node (ref "RX") (pin "2") (pinfunction "2_2") (pintype "passive"))
      (node (ref "S1") (pin "2") (pinfunction "2_2") (pintype "passive"))
      (node (ref "S2") (pin "2") (pinfunction "2_2") (pintype "passive"))
      (node (ref "S3") (pin "2") (pinfunction "2_2") (pintype "passive"))
      (node (ref "SERIAL4") (pin "2") (pinfunction "2_2") (pintype "passive"))
      (node (ref "SWD") (pin "2") (pinfunction "2_2") (pintype "passive"))
      (node (ref "TELEMETRY") (pin "2") (pinfunction "2_2") (pintype "passive"))
      (node (ref "U1") (pin "3") (pinfunction "VIN_3") (pintype "input"))
      (node (ref "U2") (pin "19") (pinfunction "VCCB_19") (pintype "power_in"))
      (node (ref "U6") (pin "19") (pinfunction "VCCB_19") (pintype "power_in"))
      (node (ref "USB") (pin "1") (pinfunction "1_1") (pintype "passive"))
      (node (ref "Z1") (pin "1") (pinfunction "K_1") (pintype "bidirectional"))
      (node (ref "ZERO_SWITCH") (pin "L2") (pinfunction "L2_L2") (pintype "bidirectional"))
    )
    (net (code "44") (name "ADC1") (class "Default")
      (node (ref "ADC1") (pin "3") (pinfunction "3_3") (pintype "passive"))
      (node (ref "IC1") (pin "34") (pinfunction "PC5_34") (pintype "bidirectional"))
    )
    (net (code "45") (name "ADC2") (class "Default")
      (node (ref "ADC2") (pin "3") (pinfunction "3_3") (pintype "passive"))
      (node (ref "IC1") (pin "35") (pinfunction "PB0_35") (pintype "bidirectional"))
    )
    (net (code "46") (name "ADC3") (class "Default")
      (node (ref "ADC3") (pin "3") (pinfunction "3_3") (pintype "passive"))
      (node (ref "IC1") (pin "36") (pinfunction "PB1_36") (pintype "bidirectional"))
    )
    (net (code "47") (name "GND") (class "Default")
      (node (ref "ADC1") (pin "1") (pinfunction "1_1") (pintype "passive"))
      (node (ref "ADC2") (pin "1") (pinfunction "1_1") (pintype "passive"))
      (node (ref "ADC3") (pin "1") (pinfunction "1_1") (pintype "passive"))
      (node (ref "BOOT") (pin "L1") (pinfunction "L1_L1") (pintype "bidirectional"))
      (node (ref "C1") (pin "2") (pinfunction "2_2") (pintype "passive"))
      (node (ref "C10") (pin "2") (pinfunction "2_2") (pintype "passive"))
      (node (ref "C11") (pin "1") (pinfunction "1_1") (pintype "passive"))
      (node (ref "C12") (pin "1") (pinfunction "1_1") (pintype "passive"))
      (node (ref "C13") (pin "2") (pinfunction "2_2") (pintype "passive"))
      (node (ref "C14") (pin "2") (pinfunction "2_2") (pintype "passive"))
      (node (ref "C15") (pin "2") (pinfunction "2_2") (pintype "passive"))
      (node (ref "C16") (pin "2") (pinfunction "2_2") (pintype "passive"))
      (node (ref "C17") (pin "2") (pinfunction "2_2") (pintype "passive"))
      (node (ref "C18") (pin "1") (pinfunction "1_1") (pintype "passive"))
      (node (ref "C19") (pin "2") (pinfunction "2_2") (pintype "passive"))
      (node (ref "C2") (pin "2") (pinfunction "2_2") (pintype "passive"))
      (node (ref "C20") (pin "2") (pinfunction "2_2") (pintype "passive"))
      (node (ref "C21") (pin "2") (pinfunction "2_2") (pintype "passive"))
      (node (ref "C22") (pin "2") (pinfunction "2_2") (pintype "passive"))
      (node (ref "C23") (pin "1") (pinfunction "1_1") (pintype "passive"))
      (node (ref "C24") (pin "1") (pinfunction "1_1") (pintype "passive"))
      (node (ref "C25") (pin "2") (pinfunction "2_2") (pintype "passive"))
      (node (ref "C26") (pin "2") (pinfunction "2_2") (pintype "passive"))
      (node (ref "C27") (pin "1") (pinfunction "1_1") (pintype "passive"))
      (node (ref "C28") (pin "1") (pinfunction "1_1") (pintype "passive"))
      (node (ref "C29") (pin "1") (pinfunction "1_1") (pintype "passive"))
      (node (ref "C3") (pin "2") (pinfunction "2_2") (pintype "passive"))
      (node (ref "C30") (pin "1") (pinfunction "1_1") (pintype "passive"))
      (node (ref "C31") (pin "1") (pinfunction "1_1") (pintype "passive"))
      (node (ref "C4") (pin "2") (pinfunction "2_2") (pintype "passive"))
      (node (ref "C5") (pin "2") (pinfunction "2_2") (pintype "passive"))
      (node (ref "C6") (pin "2") (pinfunction "2_2") (pintype "passive"))
      (node (ref "C7") (pin "2") (pinfunction "2_2") (pintype "passive"))
      (node (ref "C8") (pin "2") (pinfunction "2_2") (pintype "passive"))
      (node (ref "C9") (pin "2") (pinfunction "2_2") (pintype "passive"))
      (node (ref "D2") (pin "A") (pinfunction "A_A") (pintype "passive"))
      (node (ref "D4") (pin "A") (pinfunction "A_A") (pintype "passive"))
      (node (ref "GPS") (pin "1") (pinfunction "1_1") (pintype "passive"))
      (node (ref "I2C") (pin "1") (pinfunction "1_1") (pintype "passive"))
      (node (ref "I2C_PAR") (pin "1") (pinfunction "1_1") (pintype "passive"))
      (node (ref "IC1") (pin "10") (pinfunction "VSS_1_10") (pintype "power_in"))
      (node (ref "IC1") (pin "20") (pinfunction "VSSA_20") (pintype "power_in"))
      (node (ref "IC1") (pin "27") (pinfunction "VSS_2_27") (pintype "power_in"))
      (node (ref "IC1") (pin "37") (pinfunction "PB2_37") (pintype "bidirectional"))
      (node (ref "IC1") (pin "74") (pinfunction "VSS_3_74") (pintype "power_in"))
      (node (ref "IC1") (pin "99") (pinfunction "VSS_4_99") (pintype "power_in"))
      (node (ref "IC2") (pin "4") (pinfunction "VSS_4") (pintype "bidirectional"))
      (node (ref "IC3") (pin "18") (pinfunction "GND_18") (pintype "power_in"))
      (node (ref "IC3") (pin "21") (pinfunction "GND_21") (pintype "power_in"))
      (node (ref "IC3") (pin "25") (pinfunction "AGND_25") (pintype "power_in"))
      (node (ref "IC3") (pin "7") (pinfunction "GND_7") (pintype "power_in"))
      (node (ref "J1") (pin "-") (pinfunction "NEG_-") (pintype "passive"))
      (node (ref "LED1") (pin "2") (pinfunction "2_2") (pintype "passive"))
      (node (ref "LED2") (pin "1") (pinfunction "RED_CATHODE_1") (pintype "bidirectional"))
      (node (ref "LED2") (pin "2") (pinfunction "GREEN_CATHODE_2") (pintype "bidirectional"))
      (node (ref "LED2") (pin "3") (pinfunction "BLUE_CATHODE_3") (pintype "bidirectional"))
      (node (ref "LED5") (pin "2") (pinfunction "2_2") (pintype "passive"))
      (node (ref "MOTOR1") (pin "1") (pinfunction "1_1") (pintype "passive"))
      (node (ref "MOTOR10") (pin "1") (pinfunction "1_1") (pintype "passive"))
      (node (ref "MOTOR2") (pin "1") (pinfunction "1_1") (pintype "passive"))
      (node (ref "MOTOR3") (pin "1") (pinfunction "1_1") (pintype "passive"))
      (node (ref "MOTOR4") (pin "1") (pinfunction "1_1") (pintype "passive"))
      (node (ref "MOTOR5") (pin "1") (pinfunction "1_1") (pintype "passive"))
      (node (ref "MOTOR6") (pin "1") (pinfunction "1_1") (pintype "passive"))
      (node (ref "MOTOR7") (pin "1") (pinfunction "1_1") (pintype "passive"))
      (node (ref "MOTOR8") (pin "1") (pinfunction "1_1") (pintype "passive"))
      (node (ref "MOTOR9") (pin "1") (pinfunction "1_1") (pintype "passive"))
      (node (ref "Q1") (pin "2") (pinfunction "E_2") (pintype "passive"))
      (node (ref "RASPI_ZERO") (pin "6") (pinfunction "6_6") (pintype "passive"))
      (node (ref "RESET") (pin "P$1") (pinfunction "P$1_P$1") (pintype "passive"))
      (node (ref "RESET") (pin "P$2") (pinfunction "P$2_P$2") (pintype "passive"))
      (node (ref "RX") (pin "1") (pinfunction "1_1") (pintype "passive"))
      (node (ref "S1") (pin "1") (pinfunction "1_1") (pintype "passive"))
      (node (ref "S2") (pin "1") (pinfunction "1_1") (pintype "passive"))
      (node (ref "S3") (pin "1") (pinfunction "1_1") (pintype "passive"))
      (node (ref "SERIAL4") (pin "1") (pinfunction "1_1") (pintype "passive"))
      (node (ref "SPI_ZERO") (pin "1") (pinfunction "1_1") (pintype "passive"))
      (node (ref "SWD") (pin "1") (pinfunction "1_1") (pintype "passive"))
      (node (ref "TELEMETRY") (pin "1") (pinfunction "1_1") (pintype "passive"))
      (node (ref "U1") (pin "1") (pinfunction "ADJ/GND_1") (pintype "power_in"))
      (node (ref "U2") (pin "11") (pinfunction "GND_11") (pintype "power_in"))
      (node (ref "U3") (pin "11") (pinfunction "FSYNC_11") (pintype "bidirectional"))
      (node (ref "U3") (pin "18") (pinfunction "GND_18") (pintype "power_in"))
      (node (ref "U3") (pin "20") (pinfunction "GND_20") (pintype "power_in"))
      (node (ref "U4") (pin "3") (pinfunction "GND_3") (pintype "power_in"))
      (node (ref "U4") (pin "4") (pinfunction "CSB_4") (pintype "input"))
      (node (ref "U4") (pin "5") (pinfunction "CSB_5") (pintype "input"))
      (node (ref "U5") (pin "11") (pinfunction "GND_11") (pintype "power_in"))
      (node (ref "U6") (pin "11") (pinfunction "GND_11") (pintype "power_in"))
      (node (ref "USB") (pin "10") (pinfunction "SHIELD_10") (pintype "passive"))
      (node (ref "USB") (pin "11") (pinfunction "SHIELD_11") (pintype "passive"))
      (node (ref "USB") (pin "5") (pinfunction "5_5") (pintype "passive"))
      (node (ref "USB") (pin "6") (pinfunction "SHIELD_6") (pintype "passive"))
      (node (ref "USB") (pin "7") (pinfunction "SHIELD_7") (pintype "passive"))
      (node (ref "USB") (pin "8") (pinfunction "SHIELD_8") (pintype "passive"))
      (node (ref "USB") (pin "9") (pinfunction "SHIELD_9") (pintype "passive"))
      (node (ref "Z1") (pin "2") (pinfunction "A_2") (pintype "bidirectional"))
    )
    (net (code "48") (name "MOTOR9") (class "Default")
      (node (ref "IC1") (pin "24") (pinfunction "PA1_24") (pintype "bidirectional"))
      (node (ref "U6") (pin "1") (pinfunction "A1_1") (pintype "bidirectional"))
    )
    (net (code "49") (name "MOTOR10") (class "Default")
      (node (ref "IC1") (pin "23") (pinfunction "PA0_23") (pintype "bidirectional"))
      (node (ref "U6") (pin "3") (pinfunction "A2_3") (pintype "bidirectional"))
    )
    (net (code "50") (name "Net-(BOOT-PadCOM)") (class "Default")
      (node (ref "BOOT") (pin "COM") (pinfunction "COM_COM") (pintype "bidirectional"))
      (node (ref "R2") (pin "2") (pinfunction "2_2") (pintype "passive"))
    )
    (net (code "51") (name "Net-(D1-A2)") (class "Default")
      (node (ref "D1") (pin "2") (pinfunction "A2_2") (pintype "passive"))
      (node (ref "J1") (pin "+") (pinfunction "POS_+") (pintype "passive"))
    )
    (net (code "52") (name "Net-(D1-C)") (class "Default")
      (node (ref "C13") (pin "1") (pinfunction "1_1") (pintype "passive"))
      (node (ref "D1") (pin "3") (pinfunction "C_3") (pintype "passive"))
      (node (ref "IC1") (pin "6") (pinfunction "VBAT_6") (pintype "bidirectional"))
    )
    (net (code "53") (name "Net-(GPS-Pad3)") (class "Default")
      (node (ref "GPS") (pin "3") (pinfunction "3_3") (pintype "passive"))
      (node (ref "R28") (pin "2") (pinfunction "2_2") (pintype "passive"))
    )
    (net (code "54") (name "Net-(GPS-Pad4)") (class "Default")
      (node (ref "GPS") (pin "4") (pinfunction "4_4") (pintype "passive"))
      (node (ref "R29") (pin "2") (pinfunction "2_2") (pintype "passive"))
    )
    (net (code "55") (name "Net-(IC1-BOOT0)") (class "Default")
      (node (ref "IC1") (pin "94") (pinfunction "BOOT0_94") (pintype "bidirectional"))
      (node (ref "R2") (pin "1") (pinfunction "1_1") (pintype "passive"))
    )
    (net (code "56") (name "Net-(IC1-NRST)") (class "Default")
      (node (ref "C3") (pin "1") (pinfunction "1_1") (pintype "passive"))
      (node (ref "IC1") (pin "14") (pinfunction "NRST_14") (pintype "input"))
      (node (ref "RESET") (pin "P$3") (pinfunction "P$3_P$3") (pintype "passive"))
      (node (ref "RESET") (pin "P$4") (pinfunction "P$4_P$4") (pintype "passive"))
    )
    (net (code "57") (name "Net-(IC1-PA4)") (class "Default")
      (node (ref "IC1") (pin "29") (pinfunction "PA4_29") (pintype "bidirectional"))
      (node (ref "U3") (pin "22") (pinfunction "NCS_22") (pintype "bidirectional"))
    )
    (net (code "58") (name "Net-(IC1-PA6)") (class "Default")
      (node (ref "IC1") (pin "31") (pinfunction "PA6_31") (pintype "bidirectional"))
      (node (ref "U3") (pin "9") (pinfunction "ADO/SDO_9") (pintype "bidirectional"))
    )
    (net (code "59") (name "Net-(IC1-PA9)") (class "Default")
      (node (ref "IC1") (pin "68") (pinfunction "PA9_68") (pintype "bidirectional"))
      (node (ref "IC3") (pin "5") (pinfunction "RXD_5") (pintype "input"))
    )
    (net (code "60") (name "Net-(IC1-PA10)") (class "Default")
      (node (ref "IC1") (pin "69") (pinfunction "PA10_69") (pintype "bidirectional"))
      (node (ref "IC3") (pin "1") (pinfunction "TXD_1") (pintype "output"))
    )
    (net (code "61") (name "Net-(IC1-PA13)") (class "Default")
      (node (ref "IC1") (pin "72") (pinfunction "PA13_72") (pintype "bidirectional"))
      (node (ref "SWD") (pin "3") (pinfunction "3_3") (pintype "passive"))
    )
    (net (code "62") (name "Net-(IC1-PA14)") (class "Default")
      (node (ref "IC1") (pin "76") (pinfunction "PA14_76") (pintype "bidirectional"))
      (node (ref "SWD") (pin "4") (pinfunction "4_4") (pintype "passive"))
    )
    (net (code "63") (name "Net-(IC1-PB4)") (class "Default")
      (node (ref "IC1") (pin "90") (pinfunction "PB4_90") (pintype "bidirectional"))
      (node (ref "U2") (pin "9") (pinfunction "A8_9") (pintype "bidirectional"))
    )
    (net (code "64") (name "Net-(IC1-PB5)") (class "Default")
      (node (ref "IC1") (pin "91") (pinfunction "PB5_91") (pintype "bidirectional"))
      (node (ref "U2") (pin "8") (pinfunction "A7_8") (pintype "bidirectional"))
    )
    (net (code "65") (name "Net-(IC1-PB6)") (class "Default")
      (node (ref "IC1") (pin "92") (pinfunction "PB6_92") (pintype "bidirectional"))
      (node (ref "U2") (pin "7") (pinfunction "A6_7") (pintype "bidirectional"))
    )
    (net (code "66") (name "Net-(IC1-PB7)") (class "Default")
      (node (ref "IC1") (pin "93") (pinfunction "PB7_93") (pintype "bidirectional"))
      (node (ref "U2") (pin "6") (pinfunction "A5_6") (pintype "bidirectional"))
    )
    (net (code "67") (name "Net-(IC1-PB12)") (class "Default")
      (node (ref "IC1") (pin "51") (pinfunction "PB12_51") (pintype "bidirectional"))
      (node (ref "IC2") (pin "1") (pinfunction "~{CS}_1") (pintype "bidirectional"))
    )
    (net (code "68") (name "Net-(IC1-PB13)") (class "Default")
      (node (ref "IC1") (pin "52") (pinfunction "PB13_52") (pintype "bidirectional"))
      (node (ref "IC2") (pin "6") (pinfunction "SCK_6") (pintype "bidirectional"))
    )
    (net (code "69") (name "Net-(IC1-PB14)") (class "Default")
      (node (ref "IC1") (pin "53") (pinfunction "PB14_53") (pintype "bidirectional"))
      (node (ref "IC2") (pin "2") (pinfunction "SO_2") (pintype "bidirectional"))
    )
    (net (code "70") (name "Net-(IC1-PB15)") (class "Default")
      (node (ref "IC1") (pin "54") (pinfunction "PB15_54") (pintype "bidirectional"))
      (node (ref "IC2") (pin "5") (pinfunction "SI_5") (pintype "bidirectional"))
    )
    (net (code "71") (name "Net-(IC1-PC0)") (class "Default")
      (node (ref "IC1") (pin "15") (pinfunction "PC0_15") (pintype "bidirectional"))
      (node (ref "RX") (pin "10") (pinfunction "10_10") (pintype "passive"))
    )
    (net (code "72") (name "Net-(IC1-PC1)") (class "Default")
      (node (ref "IC1") (pin "16") (pinfunction "PC1_16") (pintype "bidirectional"))
      (node (ref "RX") (pin "9") (pinfunction "9_9") (pintype "passive"))
    )
    (net (code "73") (name "Net-(IC1-PC2)") (class "Default")
      (node (ref "IC1") (pin "17") (pinfunction "PC2_17") (pintype "bidirectional"))
      (node (ref "RX") (pin "8") (pinfunction "8_8") (pintype "passive"))
    )
    (net (code "74") (name "Net-(IC1-PC3)") (class "Default")
      (node (ref "IC1") (pin "18") (pinfunction "PC3_18") (pintype "bidirectional"))
      (node (ref "RX") (pin "7") (pinfunction "7_7") (pintype "passive"))
    )
    (net (code "75") (name "Net-(IC1-PC8)") (class "Default")
      (node (ref "IC1") (pin "65") (pinfunction "PC8_65") (pintype "bidirectional"))
      (node (ref "U2") (pin "5") (pinfunction "A4_5") (pintype "bidirectional"))
    )
    (net (code "76") (name "Net-(IC1-PC9)") (class "Default")
      (node (ref "IC1") (pin "66") (pinfunction "PC9_66") (pintype "bidirectional"))
      (node (ref "U2") (pin "4") (pinfunction "A3_4") (pintype "bidirectional"))
    )
    (net (code "77") (name "Net-(IC1-PC14)") (class "Default")
      (node (ref "C1") (pin "1") (pinfunction "1_1") (pintype "passive"))
      (node (ref "IC1") (pin "8") (pinfunction "PC14_8") (pintype "bidirectional"))
      (node (ref "Y2") (pin "2") (pinfunction "2_2") (pintype "bidirectional"))
    )
    (net (code "78") (name "Net-(IC1-PC15)") (class "Default")
      (node (ref "C2") (pin "1") (pinfunction "1_1") (pintype "passive"))
      (node (ref "IC1") (pin "9") (pinfunction "PC15_9") (pintype "bidirectional"))
      (node (ref "Y2") (pin "1") (pinfunction "1_1") (pintype "bidirectional"))
    )
    (net (code "79") (name "Net-(IC1-PD4)") (class "Default")
      (node (ref "IC1") (pin "85") (pinfunction "PD4_85") (pintype "bidirectional"))
      (node (ref "RX") (pin "6") (pinfunction "6_6") (pintype "passive"))
    )
    (net (code "80") (name "Net-(IC1-PD5)") (class "Default")
      (node (ref "IC1") (pin "86") (pinfunction "PD5_86") (pintype "bidirectional"))
      (node (ref "RX") (pin "5") (pinfunction "5_5") (pintype "passive"))
    )
    (net (code "81") (name "Net-(IC1-PD6)") (class "Default")
      (node (ref "IC1") (pin "87") (pinfunction "PD6_87") (pintype "bidirectional"))
      (node (ref "RX") (pin "4") (pinfunction "4_4") (pintype "passive"))
    )
    (net (code "82") (name "Net-(IC1-PD7)") (class "Default")
      (node (ref "IC1") (pin "88") (pinfunction "PD7_88") (pintype "bidirectional"))
      (node (ref "RX") (pin "3") (pinfunction "3_3") (pintype "passive"))
    )
    (net (code "83") (name "Net-(IC1-PD14)") (class "Default")
      (node (ref "IC1") (pin "61") (pinfunction "PD14_61") (pintype "bidirectional"))
      (node (ref "U2") (pin "3") (pinfunction "A2_3") (pintype "bidirectional"))
    )
    (net (code "84") (name "Net-(IC1-PD15)") (class "Default")
      (node (ref "IC1") (pin "62") (pinfunction "PD15_62") (pintype "bidirectional"))
      (node (ref "U2") (pin "1") (pinfunction "A1_1") (pintype "bidirectional"))
    )
    (net (code "85") (name "Net-(IC1-PE12)") (class "Default")
      (node (ref "IC1") (pin "43") (pinfunction "PE12_43") (pintype "bidirectional"))
      (node (ref "LED2") (pin "4") (pinfunction "BLUE_ANODE_4") (pintype "bidirectional"))
    )
    (net (code "86") (name "Net-(IC1-PE13)") (class "Default")
      (node (ref "IC1") (pin "44") (pinfunction "PE13_44") (pintype "bidirectional"))
      (node (ref "LED2") (pin "5") (pinfunction "GREEN_ANODE_5") (pintype "bidirectional"))
    )
    (net (code "87") (name "Net-(IC1-PE14)") (class "Default")
      (node (ref "IC1") (pin "45") (pinfunction "PE14_45") (pintype "bidirectional"))
      (node (ref "LED2") (pin "6") (pinfunction "RED_ANODE_6") (pintype "bidirectional"))
    )
    (net (code "88") (name "Net-(IC1-PH0)") (class "Default")
      (node (ref "C19") (pin "1") (pinfunction "1_1") (pintype "passive"))
      (node (ref "IC1") (pin "12") (pinfunction "PH0_12") (pintype "bidirectional"))
      (node (ref "R1") (pin "2") (pinfunction "2_2") (pintype "passive"))
      (node (ref "Y3") (pin "2") (pinfunction "2_2") (pintype "bidirectional"))
    )
    (net (code "89") (name "Net-(IC1-PH1)") (class "Default")
      (node (ref "C20") (pin "1") (pinfunction "1_1") (pintype "passive"))
      (node (ref "IC1") (pin "13") (pinfunction "PH1_13") (pintype "bidirectional"))
      (node (ref "R1") (pin "1") (pinfunction "1_1") (pintype "passive"))
      (node (ref "Y3") (pin "1") (pinfunction "1_1") (pintype "bidirectional"))
    )
    (net (code "90") (name "Net-(IC1-VCAP_1)") (class "Default")
      (node (ref "C10") (pin "1") (pinfunction "1_1") (pintype "passive"))
      (node (ref "IC1") (pin "49") (pinfunction "VCAP_1_49") (pintype "bidirectional"))
    )
    (net (code "91") (name "Net-(IC1-VCAP_2)") (class "Default")
      (node (ref "C18") (pin "2") (pinfunction "2_2") (pintype "passive"))
      (node (ref "IC1") (pin "73") (pinfunction "VCAP_2_73") (pintype "bidirectional"))
    )
    (net (code "92") (name "Net-(IC3-3V3OUT)") (class "Default")
      (node (ref "C25") (pin "1") (pinfunction "1_1") (pintype "passive"))
      (node (ref "IC3") (pin "17") (pinfunction "3V3OUT_17") (pintype "power_in"))
    )
    (net (code "93") (name "Net-(IC3-USBDM)") (class "Default")
      (node (ref "IC3") (pin "16") (pinfunction "USBDM_16") (pintype "bidirectional"))
      (node (ref "USB") (pin "2") (pinfunction "2_2") (pintype "passive"))
    )
    (net (code "94") (name "Net-(IC3-USBDP)") (class "Default")
      (node (ref "IC3") (pin "15") (pinfunction "USBDP_15") (pintype "bidirectional"))
      (node (ref "USB") (pin "3") (pinfunction "3_3") (pintype "passive"))
    )
    (net (code "95") (name "Net-(IC3-~{RXLED})") (class "Default")
      (node (ref "IC3") (pin "22") (pinfunction "~{RXLED}_22") (pintype "input"))
      (node (ref "RXL") (pin "2") (pinfunction "2_2") (pintype "passive"))
    )
    (net (code "96") (name "Net-(IC3-~{TXLED})") (class "Default")
      (node (ref "IC3") (pin "23") (pinfunction "~{TXLED}_23") (pintype "input"))
      (node (ref "TXL") (pin "2") (pinfunction "2_2") (pintype "passive"))
    )
    (net (code "97") (name "Net-(LED1-Pad1)") (class "Default")
      (node (ref "LED1") (pin "1") (pinfunction "1_1") (pintype "passive"))
      (node (ref "R4") (pin "1") (pinfunction "1_1") (pintype "passive"))
    )
    (net (code "98") (name "Net-(LED5-Pad1)") (class "Default")
      (node (ref "LED5") (pin "1") (pinfunction "1_1") (pintype "passive"))
      (node (ref "R12") (pin "1") (pinfunction "1_1") (pintype "passive"))
    )
    (net (code "99") (name "Net-(MOTOR1-Pad3)") (class "Default")
      (node (ref "MOTOR1") (pin "3") (pinfunction "3_3") (pintype "passive"))
      (node (ref "R21") (pin "1") (pinfunction "1_1") (pintype "passive"))
    )
    (net (code "100") (name "Net-(MOTOR2-Pad3)") (class "Default")
      (node (ref "MOTOR2") (pin "3") (pinfunction "3_3") (pintype "passive"))
      (node (ref "R20") (pin "1") (pinfunction "1_1") (pintype "passive"))
    )
    (net (code "101") (name "Net-(MOTOR3-Pad3)") (class "Default")
      (node (ref "MOTOR3") (pin "3") (pinfunction "3_3") (pintype "passive"))
      (node (ref "R19") (pin "1") (pinfunction "1_1") (pintype "passive"))
    )
    (net (code "102") (name "Net-(MOTOR4-Pad3)") (class "Default")
      (node (ref "MOTOR4") (pin "3") (pinfunction "3_3") (pintype "passive"))
      (node (ref "R18") (pin "1") (pinfunction "1_1") (pintype "passive"))
    )
    (net (code "103") (name "Net-(MOTOR5-Pad3)") (class "Default")
      (node (ref "MOTOR5") (pin "3") (pinfunction "3_3") (pintype "passive"))
      (node (ref "R17") (pin "1") (pinfunction "1_1") (pintype "passive"))
    )
    (net (code "104") (name "Net-(MOTOR6-Pad3)") (class "Default")
      (node (ref "MOTOR6") (pin "3") (pinfunction "3_3") (pintype "passive"))
      (node (ref "R16") (pin "1") (pinfunction "1_1") (pintype "passive"))
    )
    (net (code "105") (name "Net-(MOTOR7-Pad3)") (class "Default")
      (node (ref "MOTOR7") (pin "3") (pinfunction "3_3") (pintype "passive"))
      (node (ref "R15") (pin "1") (pinfunction "1_1") (pintype "passive"))
    )
    (net (code "106") (name "Net-(MOTOR8-Pad3)") (class "Default")
      (node (ref "MOTOR8") (pin "3") (pinfunction "3_3") (pintype "passive"))
      (node (ref "R14") (pin "1") (pinfunction "1_1") (pintype "passive"))
    )
    (net (code "107") (name "Net-(MOTOR9-Pad3)") (class "Default")
      (node (ref "MOTOR9") (pin "3") (pinfunction "3_3") (pintype "passive"))
      (node (ref "R9") (pin "1") (pinfunction "1_1") (pintype "passive"))
    )
    (net (code "108") (name "Net-(MOTOR10-Pad3)") (class "Default")
      (node (ref "MOTOR10") (pin "3") (pinfunction "3_3") (pintype "passive"))
      (node (ref "R13") (pin "1") (pinfunction "1_1") (pintype "passive"))
    )
    (net (code "109") (name "Net-(Q1-B)") (class "Default")
      (node (ref "Q1") (pin "1") (pinfunction "B_1") (pintype "passive"))
      (node (ref "RESISTOR") (pin "2") (pinfunction "2_2") (pintype "passive"))
    )
    (net (code "110") (name "Net-(Q1-C)") (class "Default")
      (node (ref "BUZZER") (pin "1") (pinfunction "1_1") (pintype "passive"))
      (node (ref "Q1") (pin "3") (pinfunction "C_3") (pintype "passive"))
    )
    (net (code "111") (name "Net-(R10-Pad1)") (class "Default")
      (node (ref "R10") (pin "1") (pinfunction "1_1") (pintype "passive"))
      (node (ref "TXL") (pin "1") (pinfunction "1_1") (pintype "passive"))
    )
    (net (code "112") (name "Net-(R11-Pad1)") (class "Default")
      (node (ref "R11") (pin "1") (pinfunction "1_1") (pintype "passive"))
      (node (ref "RXL") (pin "1") (pinfunction "1_1") (pintype "passive"))
    )
    (net (code "113") (name "Net-(R22-Pad2)") (class "Default")
      (node (ref "R22") (pin "2") (pinfunction "2_2") (pintype "passive"))
      (node (ref "SERIAL4") (pin "3") (pinfunction "3_3") (pintype "passive"))
    )
    (net (code "114") (name "Net-(R23-Pad2)") (class "Default")
      (node (ref "R23") (pin "2") (pinfunction "2_2") (pintype "passive"))
      (node (ref "SERIAL4") (pin "4") (pinfunction "4_4") (pintype "passive"))
    )
    (net (code "115") (name "Net-(R26-Pad2)") (class "Default")
      (node (ref "R26") (pin "2") (pinfunction "2_2") (pintype "passive"))
      (node (ref "TELEMETRY") (pin "4") (pinfunction "4_4") (pintype "passive"))
    )
    (net (code "116") (name "Net-(R27-Pad2)") (class "Default")
      (node (ref "R27") (pin "2") (pinfunction "2_2") (pintype "passive"))
      (node (ref "TELEMETRY") (pin "3") (pinfunction "3_3") (pintype "passive"))
    )
    (net (code "117") (name "Net-(RASPI_ZERO-Pad4)") (class "Default")
      (node (ref "RASPI_ZERO") (pin "4") (pinfunction "4_4") (pintype "passive"))
      (node (ref "ZERO_SWITCH") (pin "COM") (pinfunction "COM_COM") (pintype "bidirectional"))
    )
    (net (code "118") (name "Net-(U3-REGOUT)") (class "Default")
      (node (ref "C21") (pin "1") (pinfunction "1_1") (pintype "passive"))
      (node (ref "U3") (pin "10") (pinfunction "REGOUT_10") (pintype "bidirectional"))
    )
    (net (code "119") (name "Net-(X1A-S)") (class "Default")
      (node (ref "D4") (pin "C") (pinfunction "C_C") (pintype "passive"))
      (node (ref "D5") (pin "A") (pinfunction "A_A") (pintype "passive"))
      (node (ref "X1") (pin "1") (pinfunction "S_1") (pintype "passive"))
    )
    (net (code "120") (name "Net-(X1B-S)") (class "Default")
      (node (ref "D2") (pin "C") (pinfunction "C_C") (pintype "passive"))
      (node (ref "D3") (pin "A") (pinfunction "A_A") (pintype "passive"))
      (node (ref "X1") (pin "2") (pinfunction "S_2") (pintype "passive"))
    )
    (net (code "121") (name "PB10") (class "Default")
      (node (ref "IC1") (pin "47") (pinfunction "PB10_47") (pintype "bidirectional"))
      (node (ref "R6") (pin "2") (pinfunction "2_2") (pintype "passive"))
      (node (ref "U4") (pin "8") (pinfunction "SCLK_8") (pintype "input"))
    )
    (net (code "122") (name "PB11") (class "Default")
      (node (ref "IC1") (pin "48") (pinfunction "PB11_48") (pintype "bidirectional"))
      (node (ref "R5") (pin "2") (pinfunction "2_2") (pintype "passive"))
      (node (ref "U4") (pin "7") (pinfunction "SDI/SDA_7") (pintype "bidirectional"))
    )
    (net (code "123") (name "VCC3V3") (class "Default")
      (node (ref "BOOT") (pin "L2") (pinfunction "L2_L2") (pintype "bidirectional"))
      (node (ref "C11") (pin "2") (pinfunction "2_2") (pintype "passive"))
      (node (ref "C12") (pin "2") (pinfunction "2_2") (pintype "passive"))
      (node (ref "C14") (pin "1") (pinfunction "1_1") (pintype "passive"))
      (node (ref "C15") (pin "1") (pinfunction "1_1") (pintype "passive"))
      (node (ref "C16") (pin "1") (pinfunction "1_1") (pintype "passive"))
      (node (ref "C17") (pin "1") (pinfunction "1_1") (pintype "passive"))
      (node (ref "C22") (pin "1") (pinfunction "1_1") (pintype "passive"))
      (node (ref "C23") (pin "2") (pinfunction "2_2") (pintype "passive"))
      (node (ref "C24") (pin "2") (pinfunction "2_2") (pintype "passive"))
      (node (ref "C26") (pin "1") (pinfunction "1_1") (pintype "passive"))
      (node (ref "C28") (pin "2") (pinfunction "2_2") (pintype "passive"))
      (node (ref "C29") (pin "2") (pinfunction "2_2") (pintype "passive"))
      (node (ref "C30") (pin "2") (pinfunction "2_2") (pintype "passive"))
      (node (ref "C31") (pin "2") (pinfunction "2_2") (pintype "passive"))
      (node (ref "C6") (pin "1") (pinfunction "1_1") (pintype "passive"))
      (node (ref "C7") (pin "1") (pinfunction "1_1") (pintype "passive"))
      (node (ref "C8") (pin "1") (pinfunction "1_1") (pintype "passive"))
      (node (ref "C9") (pin "1") (pinfunction "1_1") (pintype "passive"))
      (node (ref "D1") (pin "1") (pinfunction "A1_1") (pintype "passive"))
      (node (ref "IC1") (pin "100") (pinfunction "VDD_6_100") (pintype "power_in"))
      (node (ref "IC1") (pin "11") (pinfunction "VDD_1_11") (pintype "power_in"))
      (node (ref "IC1") (pin "19") (pinfunction "VDD_2_19") (pintype "power_in"))
      (node (ref "IC1") (pin "21") (pinfunction "VREF+_21") (pintype "input"))
      (node (ref "IC1") (pin "22") (pinfunction "VDDA_22") (pintype "power_in"))
      (node (ref "IC1") (pin "28") (pinfunction "VDD_3_28") (pintype "power_in"))
      (node (ref "IC1") (pin "50") (pinfunction "VDD_4_50") (pintype "power_in"))
      (node (ref "IC1") (pin "75") (pinfunction "VDD_5_75") (pintype "power_in"))
      (node (ref "IC2") (pin "3") (pinfunction "~{WP}_3") (pintype "bidirectional"))
      (node (ref "IC2") (pin "7") (pinfunction "~{HOLD}_7") (pintype "bidirectional"))
      (node (ref "IC2") (pin "8") (pinfunction "VDD_8") (pintype "bidirectional"))
      (node (ref "R5") (pin "1") (pinfunction "1_1") (pintype "passive"))
      (node (ref "R6") (pin "1") (pinfunction "1_1") (pintype "passive"))
      (node (ref "R7") (pin "2") (pinfunction "2_2") (pintype "passive"))
      (node (ref "R8") (pin "2") (pinfunction "2_2") (pintype "passive"))
      (node (ref "SPI_ZERO") (pin "2") (pinfunction "2_2") (pintype "passive"))
      (node (ref "U1") (pin "2") (pinfunction "VOUT_2") (pintype "output"))
      (node (ref "U2") (pin "10") (pinfunction "OE_10") (pintype "input"))
      (node (ref "U2") (pin "2") (pinfunction "VCCA_2") (pintype "power_in"))
      (node (ref "U3") (pin "1") (pinfunction "RESV1_1") (pintype "power_in"))
      (node (ref "U3") (pin "13") (pinfunction "VDD_13") (pintype "power_in"))
      (node (ref "U3") (pin "8") (pinfunction "VDDIO_8") (pintype "power_in"))
      (node (ref "U4") (pin "1") (pinfunction "VDD_1") (pintype "power_in"))
      (node (ref "U4") (pin "2") (pinfunction "PS_2") (pintype "input"))
      (node (ref "U5") (pin "10") (pinfunction "OE_10") (pintype "input"))
      (node (ref "U5") (pin "19") (pinfunction "VCCB_19") (pintype "power_in"))
      (node (ref "U5") (pin "2") (pinfunction "VCCA_2") (pintype "power_in"))
      (node (ref "U6") (pin "10") (pinfunction "OE_10") (pintype "input"))
      (node (ref "U6") (pin "2") (pinfunction "VCCA_2") (pintype "power_in"))
    )
    (net (code "124") (name "unconnected-(IC1-PA8-Pad67)") (class "Default")
      (node (ref "IC1") (pin "67") (pinfunction "PA8_67") (pintype "bidirectional"))
    )
    (net (code "125") (name "unconnected-(IC1-PA11-Pad70)") (class "Default")
      (node (ref "IC1") (pin "70") (pinfunction "PA11_70") (pintype "bidirectional"))
    )
    (net (code "126") (name "unconnected-(IC1-PA12-Pad71)") (class "Default")
      (node (ref "IC1") (pin "71") (pinfunction "PA12_71") (pintype "bidirectional"))
    )
    (net (code "127") (name "unconnected-(IC1-PA15-Pad77)") (class "Default")
      (node (ref "IC1") (pin "77") (pinfunction "PA15_77") (pintype "bidirectional"))
    )
    (net (code "128") (name "unconnected-(IC1-PB3-Pad89)") (class "Default")
      (node (ref "IC1") (pin "89") (pinfunction "PB3_89") (pintype "bidirectional"))
    )
    (net (code "129") (name "unconnected-(IC1-PC4-Pad33)") (class "Default")
      (node (ref "IC1") (pin "33") (pinfunction "PC4_33") (pintype "bidirectional"))
    )
    (net (code "130") (name "unconnected-(IC1-PC6-Pad63)") (class "Default")
      (node (ref "IC1") (pin "63") (pinfunction "PC6_63") (pintype "bidirectional"))
    )
    (net (code "131") (name "unconnected-(IC1-PC7-Pad64)") (class "Default")
      (node (ref "IC1") (pin "64") (pinfunction "PC7_64") (pintype "bidirectional"))
    )
    (net (code "132") (name "unconnected-(IC1-PC13-Pad7)") (class "Default")
      (node (ref "IC1") (pin "7") (pinfunction "PC13_7") (pintype "bidirectional"))
    )
    (net (code "133") (name "unconnected-(IC1-PD0-Pad81)") (class "Default")
      (node (ref "IC1") (pin "81") (pinfunction "PD0_81") (pintype "bidirectional"))
    )
    (net (code "134") (name "unconnected-(IC1-PD1-Pad82)") (class "Default")
      (node (ref "IC1") (pin "82") (pinfunction "PD1_82") (pintype "bidirectional"))
    )
    (net (code "135") (name "unconnected-(IC1-PD3-Pad84)") (class "Default")
      (node (ref "IC1") (pin "84") (pinfunction "PD3_84") (pintype "bidirectional"))
    )
    (net (code "136") (name "unconnected-(IC1-PD10-Pad57)") (class "Default")
      (node (ref "IC1") (pin "57") (pinfunction "PD10_57") (pintype "bidirectional"))
    )
    (net (code "137") (name "unconnected-(IC1-PD11-Pad58)") (class "Default")
      (node (ref "IC1") (pin "58") (pinfunction "PD11_58") (pintype "bidirectional"))
    )
    (net (code "138") (name "unconnected-(IC1-PD12-Pad59)") (class "Default")
      (node (ref "IC1") (pin "59") (pinfunction "PD12_59") (pintype "bidirectional"))
    )
    (net (code "139") (name "unconnected-(IC1-PE0-Pad97)") (class "Default")
      (node (ref "IC1") (pin "97") (pinfunction "PE0_97") (pintype "bidirectional"))
    )
    (net (code "140") (name "unconnected-(IC1-PE1-Pad98)") (class "Default")
      (node (ref "IC1") (pin "98") (pinfunction "PE1_98") (pintype "bidirectional"))
    )
    (net (code "141") (name "unconnected-(IC1-PE2-Pad1)") (class "Default")
      (node (ref "IC1") (pin "1") (pinfunction "PE2_1") (pintype "bidirectional"))
    )
    (net (code "142") (name "unconnected-(IC1-PE3-Pad2)") (class "Default")
      (node (ref "IC1") (pin "2") (pinfunction "PE3_2") (pintype "bidirectional"))
    )
    (net (code "143") (name "unconnected-(IC1-PE4-Pad3)") (class "Default")
      (node (ref "IC1") (pin "3") (pinfunction "PE4_3") (pintype "bidirectional"))
    )
    (net (code "144") (name "unconnected-(IC1-PE5-Pad4)") (class "Default")
      (node (ref "IC1") (pin "4") (pinfunction "PE5_4") (pintype "bidirectional"))
    )
    (net (code "145") (name "unconnected-(IC1-PE6-Pad5)") (class "Default")
      (node (ref "IC1") (pin "5") (pinfunction "PE6_5") (pintype "bidirectional"))
    )
    (net (code "146") (name "unconnected-(IC1-PE7-Pad38)") (class "Default")
      (node (ref "IC1") (pin "38") (pinfunction "PE7_38") (pintype "bidirectional"))
    )
    (net (code "147") (name "unconnected-(IC1-PE15-Pad46)") (class "Default")
      (node (ref "IC1") (pin "46") (pinfunction "PE15_46") (pintype "bidirectional"))
    )
    (net (code "148") (name "unconnected-(IC3-OSCI-Pad27)") (class "Default")
      (node (ref "IC3") (pin "27") (pinfunction "OSCI_27") (pintype "no_connect"))
    )
    (net (code "149") (name "unconnected-(IC3-OSCO-Pad28)") (class "Default")
      (node (ref "IC3") (pin "28") (pinfunction "OSCO_28") (pintype "output"))
    )
    (net (code "150") (name "unconnected-(IC3-TEST-Pad26)") (class "Default")
      (node (ref "IC3") (pin "26") (pinfunction "TEST_26") (pintype "input"))
    )
    (net (code "151") (name "unconnected-(IC3-TXDEN-Pad13)") (class "Default")
      (node (ref "IC3") (pin "13") (pinfunction "TXDEN_13") (pintype "no_connect"))
    )
    (net (code "152") (name "unconnected-(IC3-~{CTS}-Pad11)") (class "Default")
      (node (ref "IC3") (pin "11") (pinfunction "~{CTS}_11") (pintype "input"))
    )
    (net (code "153") (name "unconnected-(IC3-~{DCD}-Pad10)") (class "Default")
      (node (ref "IC3") (pin "10") (pinfunction "~{DCD}_10") (pintype "no_connect"))
    )
    (net (code "154") (name "unconnected-(IC3-~{DSR}-Pad9)") (class "Default")
      (node (ref "IC3") (pin "9") (pinfunction "~{DSR}_9") (pintype "no_connect"))
    )
    (net (code "155") (name "unconnected-(IC3-~{DTR}-Pad2)") (class "Default")
      (node (ref "IC3") (pin "2") (pinfunction "~{DTR}_2") (pintype "output"))
    )
    (net (code "156") (name "unconnected-(IC3-~{PWREN}-Pad14)") (class "Default")
      (node (ref "IC3") (pin "14") (pinfunction "~{PWREN}_14") (pintype "no_connect"))
    )
    (net (code "157") (name "unconnected-(IC3-~{RESET}-Pad19)") (class "Default")
      (node (ref "IC3") (pin "19") (pinfunction "~{RESET}_19") (pintype "no_connect"))
    )
    (net (code "158") (name "unconnected-(IC3-~{RI}-Pad6)") (class "Default")
      (node (ref "IC3") (pin "6") (pinfunction "~{RI}_6") (pintype "no_connect"))
    )
    (net (code "159") (name "unconnected-(IC3-~{RTS}-Pad3)") (class "Default")
      (node (ref "IC3") (pin "3") (pinfunction "~{RTS}_3") (pintype "output"))
    )
    (net (code "160") (name "unconnected-(IC3-~{SLEEP}-Pad12)") (class "Default")
      (node (ref "IC3") (pin "12") (pinfunction "~{SLEEP}_12") (pintype "no_connect"))
    )
    (net (code "161") (name "unconnected-(RASPI_ZERO-Pad1)") (class "Default")
      (node (ref "RASPI_ZERO") (pin "1") (pinfunction "1_1") (pintype "passive"))
    )
    (net (code "162") (name "unconnected-(RASPI_ZERO-Pad2)") (class "Default")
      (node (ref "RASPI_ZERO") (pin "2") (pinfunction "2_2") (pintype "passive"))
    )
    (net (code "163") (name "unconnected-(RASPI_ZERO-Pad7)") (class "Default")
      (node (ref "RASPI_ZERO") (pin "7") (pinfunction "7_7") (pintype "passive"))
    )
    (net (code "164") (name "unconnected-(RASPI_ZERO-Pad9)") (class "Default")
      (node (ref "RASPI_ZERO") (pin "9") (pinfunction "9_9") (pintype "passive"))
    )
    (net (code "165") (name "unconnected-(RASPI_ZERO-Pad11)") (class "Default")
      (node (ref "RASPI_ZERO") (pin "11") (pinfunction "11_11") (pintype "passive"))
    )
    (net (code "166") (name "unconnected-(RASPI_ZERO-Pad12)") (class "Default")
      (node (ref "RASPI_ZERO") (pin "12") (pinfunction "12_12") (pintype "passive"))
    )
    (net (code "167") (name "unconnected-(RASPI_ZERO-Pad13)") (class "Default")
      (node (ref "RASPI_ZERO") (pin "13") (pinfunction "13_13") (pintype "passive"))
    )
    (net (code "168") (name "unconnected-(RASPI_ZERO-Pad14)") (class "Default")
      (node (ref "RASPI_ZERO") (pin "14") (pinfunction "14_14") (pintype "passive"))
    )
    (net (code "169") (name "unconnected-(RASPI_ZERO-Pad16)") (class "Default")
      (node (ref "RASPI_ZERO") (pin "16") (pinfunction "16_16") (pintype "passive"))
    )
    (net (code "170") (name "unconnected-(RASPI_ZERO-Pad17)") (class "Default")
      (node (ref "RASPI_ZERO") (pin "17") (pinfunction "17_17") (pintype "passive"))
    )
    (net (code "171") (name "unconnected-(RASPI_ZERO-Pad18)") (class "Default")
      (node (ref "RASPI_ZERO") (pin "18") (pinfunction "18_18") (pintype "passive"))
    )
    (net (code "172") (name "unconnected-(RASPI_ZERO-Pad20)") (class "Default")
      (node (ref "RASPI_ZERO") (pin "20") (pinfunction "20_20") (pintype "passive"))
    )
    (net (code "173") (name "unconnected-(RASPI_ZERO-Pad22)") (class "Default")
      (node (ref "RASPI_ZERO") (pin "22") (pinfunction "22_22") (pintype "passive"))
    )
    (net (code "174") (name "unconnected-(RASPI_ZERO-Pad24)") (class "Default")
      (node (ref "RASPI_ZERO") (pin "24") (pinfunction "24_24") (pintype "passive"))
    )
    (net (code "175") (name "unconnected-(RASPI_ZERO-Pad25)") (class "Default")
      (node (ref "RASPI_ZERO") (pin "25") (pinfunction "25_25") (pintype "passive"))
    )
    (net (code "176") (name "unconnected-(RASPI_ZERO-Pad26)") (class "Default")
      (node (ref "RASPI_ZERO") (pin "26") (pinfunction "26_26") (pintype "passive"))
    )
    (net (code "177") (name "unconnected-(RASPI_ZERO-Pad27)") (class "Default")
      (node (ref "RASPI_ZERO") (pin "27") (pinfunction "27_27") (pintype "passive"))
    )
    (net (code "178") (name "unconnected-(RASPI_ZERO-Pad28)") (class "Default")
      (node (ref "RASPI_ZERO") (pin "28") (pinfunction "28_28") (pintype "passive"))
    )
    (net (code "179") (name "unconnected-(RASPI_ZERO-Pad29)") (class "Default")
      (node (ref "RASPI_ZERO") (pin "29") (pinfunction "29_29") (pintype "passive"))
    )
    (net (code "180") (name "unconnected-(RASPI_ZERO-Pad30)") (class "Default")
      (node (ref "RASPI_ZERO") (pin "30") (pinfunction "30_30") (pintype "passive"))
    )
    (net (code "181") (name "unconnected-(RASPI_ZERO-Pad31)") (class "Default")
      (node (ref "RASPI_ZERO") (pin "31") (pinfunction "31_31") (pintype "passive"))
    )
    (net (code "182") (name "unconnected-(RASPI_ZERO-Pad32)") (class "Default")
      (node (ref "RASPI_ZERO") (pin "32") (pinfunction "32_32") (pintype "passive"))
    )
    (net (code "183") (name "unconnected-(RASPI_ZERO-Pad33)") (class "Default")
      (node (ref "RASPI_ZERO") (pin "33") (pinfunction "33_33") (pintype "passive"))
    )
    (net (code "184") (name "unconnected-(RASPI_ZERO-Pad34)") (class "Default")
      (node (ref "RASPI_ZERO") (pin "34") (pinfunction "34_34") (pintype "passive"))
    )
    (net (code "185") (name "unconnected-(RASPI_ZERO-Pad35)") (class "Default")
      (node (ref "RASPI_ZERO") (pin "35") (pinfunction "35_35") (pintype "passive"))
    )
    (net (code "186") (name "unconnected-(RASPI_ZERO-Pad36)") (class "Default")
      (node (ref "RASPI_ZERO") (pin "36") (pinfunction "36_36") (pintype "passive"))
    )
    (net (code "187") (name "unconnected-(RASPI_ZERO-Pad37)") (class "Default")
      (node (ref "RASPI_ZERO") (pin "37") (pinfunction "37_37") (pintype "passive"))
    )
    (net (code "188") (name "unconnected-(RASPI_ZERO-Pad38)") (class "Default")
      (node (ref "RASPI_ZERO") (pin "38") (pinfunction "38_38") (pintype "passive"))
    )
    (net (code "189") (name "unconnected-(RASPI_ZERO-Pad39)") (class "Default")
      (node (ref "RASPI_ZERO") (pin "39") (pinfunction "39_39") (pintype "passive"))
    )
    (net (code "190") (name "unconnected-(RASPI_ZERO-Pad40)") (class "Default")
      (node (ref "RASPI_ZERO") (pin "40") (pinfunction "40_40") (pintype "passive"))
    )
    (net (code "191") (name "unconnected-(U3-AUX_CL-Pad7)") (class "Default")
      (node (ref "U3") (pin "7") (pinfunction "AUX_CL_7") (pintype "bidirectional"))
    )
    (net (code "192") (name "unconnected-(U3-AUX_DA-Pad21)") (class "Default")
      (node (ref "U3") (pin "21") (pinfunction "AUX_DA_21") (pintype "bidirectional"))
    )
    (net (code "193") (name "unconnected-(U4-SDO-Pad6)") (class "Default")
      (node (ref "U4") (pin "6") (pinfunction "SDO_6") (pintype "output"))
    )
    (net (code "194") (name "unconnected-(U6-A3-Pad4)") (class "Default")
      (node (ref "U6") (pin "4") (pinfunction "A3_4") (pintype "bidirectional"))
    )
    (net (code "195") (name "unconnected-(U6-A4-Pad5)") (class "Default")
      (node (ref "U6") (pin "5") (pinfunction "A4_5") (pintype "bidirectional"))
    )
    (net (code "196") (name "unconnected-(U6-A5-Pad6)") (class "Default")
      (node (ref "U6") (pin "6") (pinfunction "A5_6") (pintype "bidirectional"))
    )
    (net (code "197") (name "unconnected-(U6-A6-Pad7)") (class "Default")
      (node (ref "U6") (pin "7") (pinfunction "A6_7") (pintype "bidirectional"))
    )
    (net (code "198") (name "unconnected-(U6-A7-Pad8)") (class "Default")
      (node (ref "U6") (pin "8") (pinfunction "A7_8") (pintype "bidirectional"))
    )
    (net (code "199") (name "unconnected-(U6-A8-Pad9)") (class "Default")
      (node (ref "U6") (pin "9") (pinfunction "A8_9") (pintype "bidirectional"))
    )
    (net (code "200") (name "unconnected-(U6-B3-Pad17)") (class "Default")
      (node (ref "U6") (pin "17") (pinfunction "B3_17") (pintype "bidirectional"))
    )
    (net (code "201") (name "unconnected-(U6-B4-Pad16)") (class "Default")
      (node (ref "U6") (pin "16") (pinfunction "B4_16") (pintype "bidirectional"))
    )
    (net (code "202") (name "unconnected-(U6-B5-Pad15)") (class "Default")
      (node (ref "U6") (pin "15") (pinfunction "B5_15") (pintype "bidirectional"))
    )
    (net (code "203") (name "unconnected-(U6-B6-Pad14)") (class "Default")
      (node (ref "U6") (pin "14") (pinfunction "B6_14") (pintype "bidirectional"))
    )
    (net (code "204") (name "unconnected-(U6-B7-Pad13)") (class "Default")
      (node (ref "U6") (pin "13") (pinfunction "B7_13") (pintype "bidirectional"))
    )
    (net (code "205") (name "unconnected-(U6-B8-Pad12)") (class "Default")
      (node (ref "U6") (pin "12") (pinfunction "B8_12") (pintype "bidirectional"))
    )
    (net (code "206") (name "unconnected-(USB-Pad4)") (class "Default")
      (node (ref "USB") (pin "4") (pinfunction "4_4") (pintype "passive"))
    )
    (net (code "207") (name "unconnected-(ZERO_SWITCH-PadL1)") (class "Default")
      (node (ref "ZERO_SWITCH") (pin "L1") (pinfunction "L1_L1") (pintype "bidirectional"))
    )
  )
)
